# BlueBus.net
KiCad netlist of a schematic drawn in EAGLE
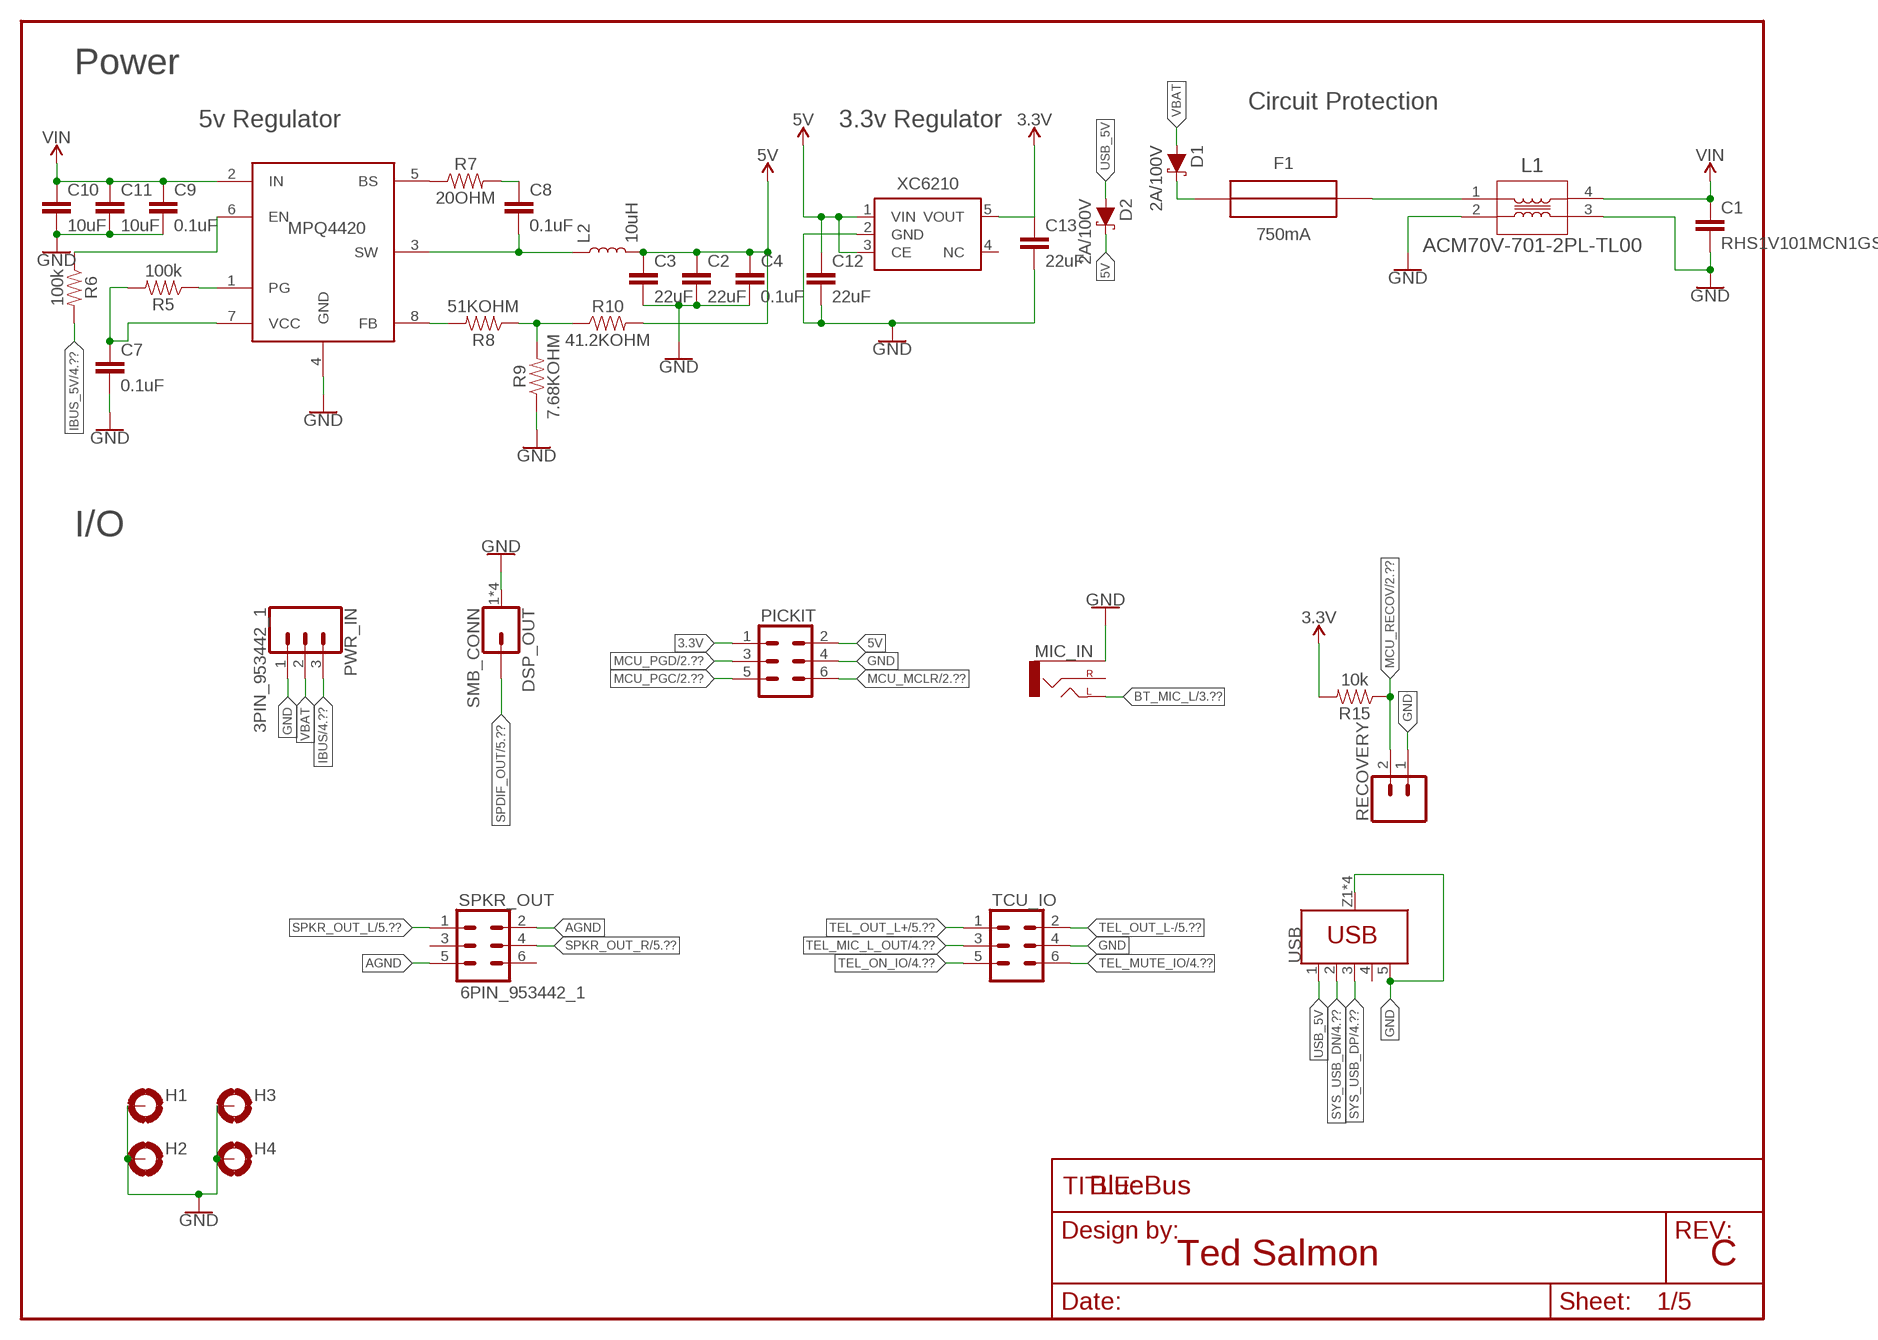
[diagram p0: schematic, sheet 1]
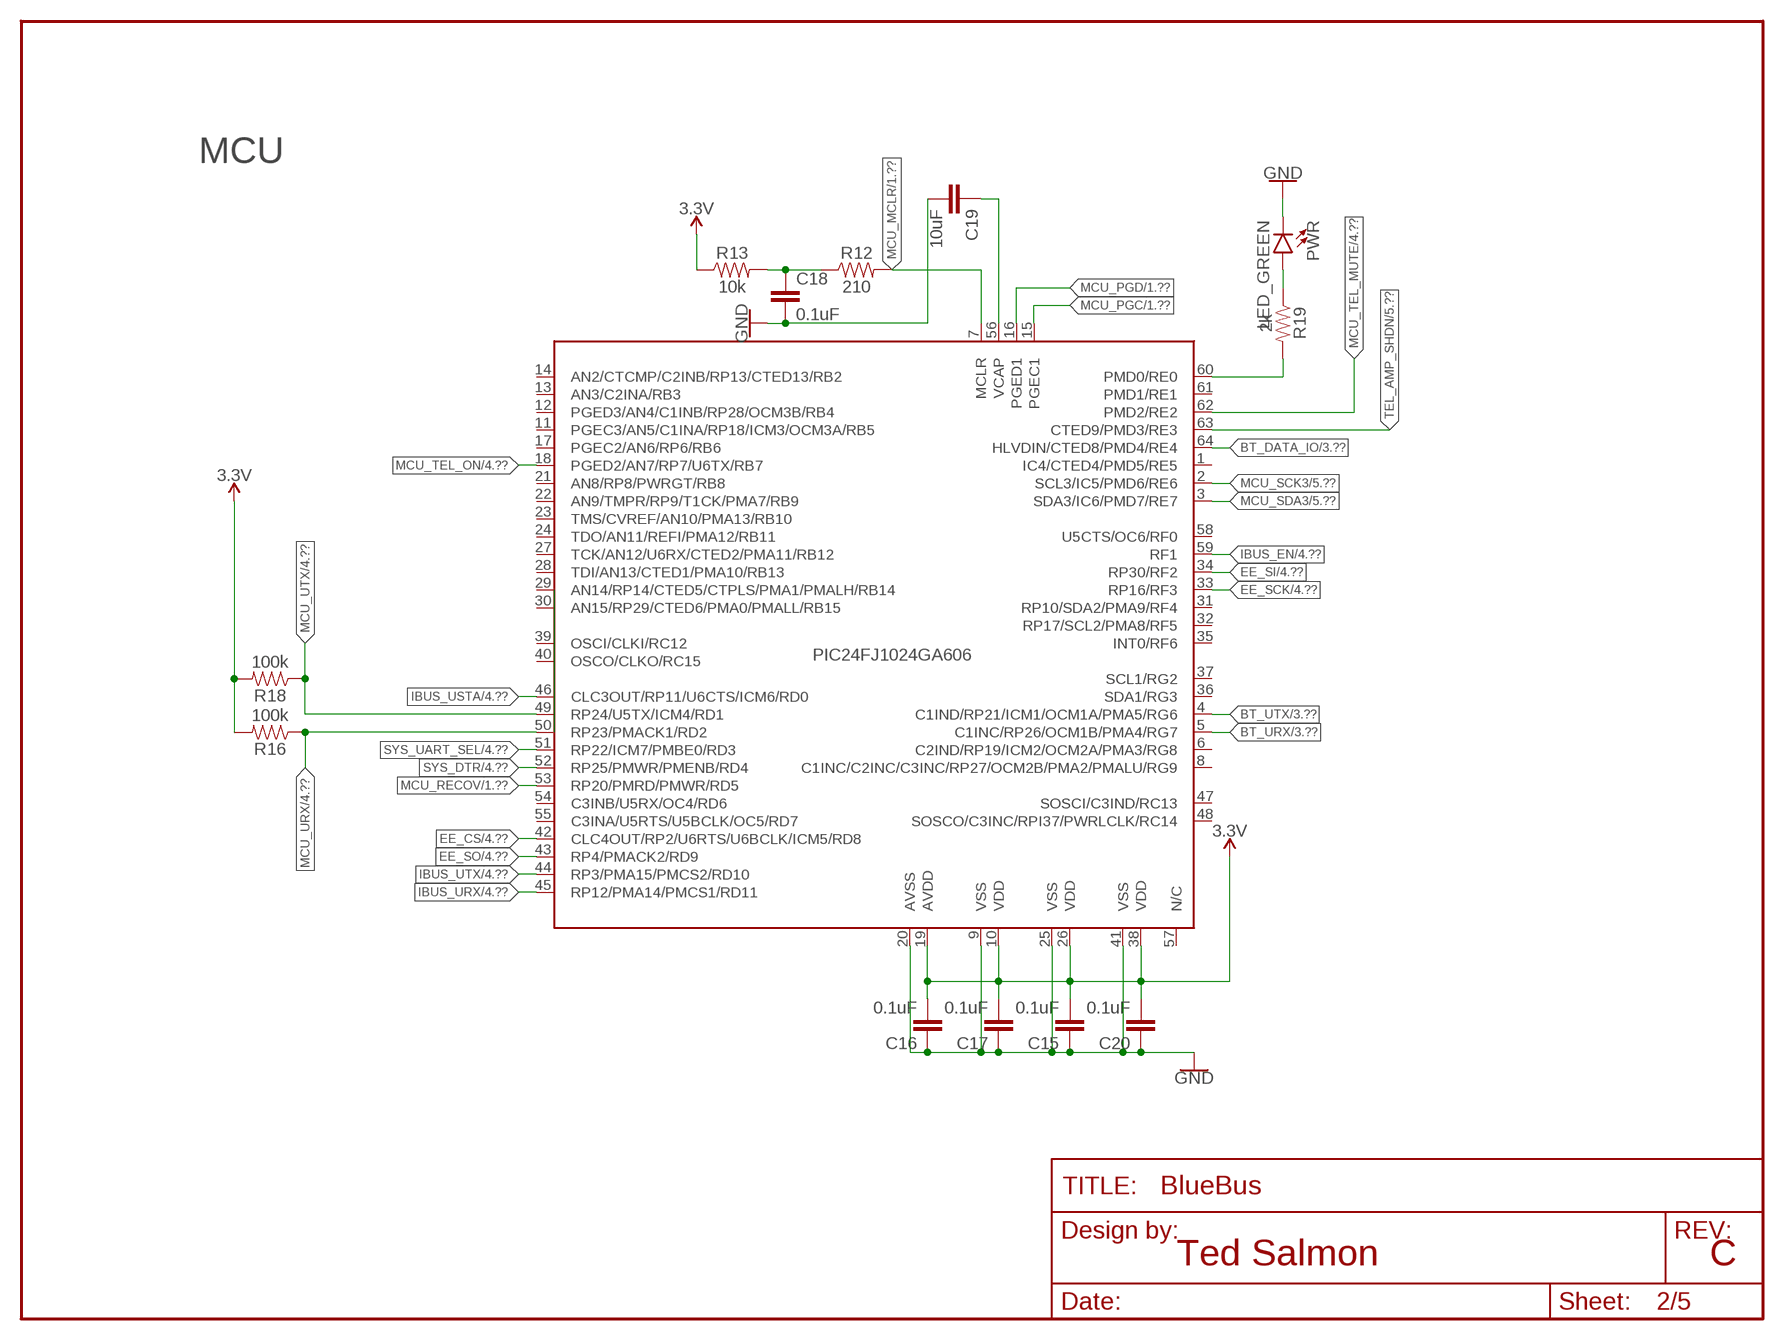
[diagram p1: schematic, sheet 2]
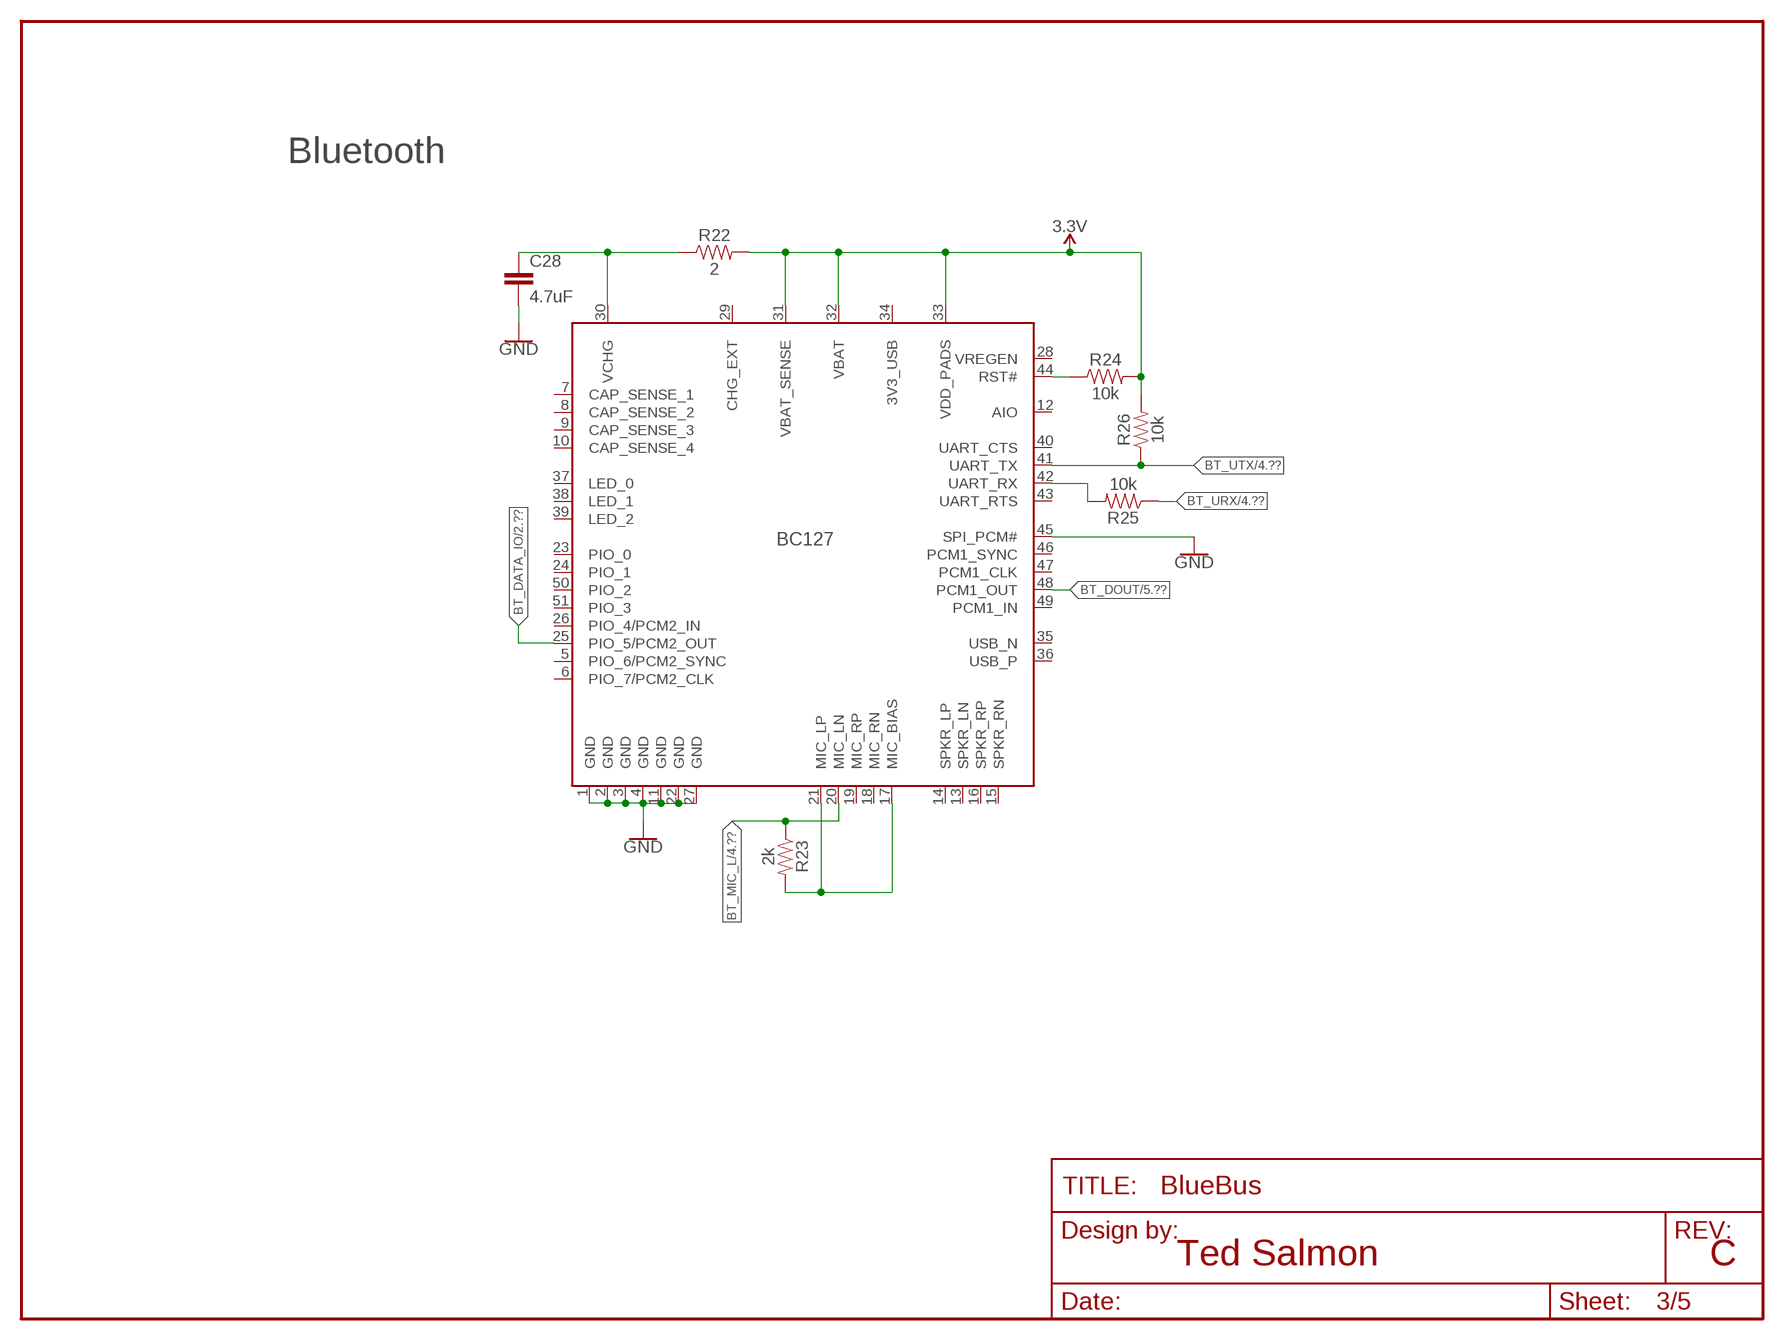
[diagram p2: schematic, sheet 3]
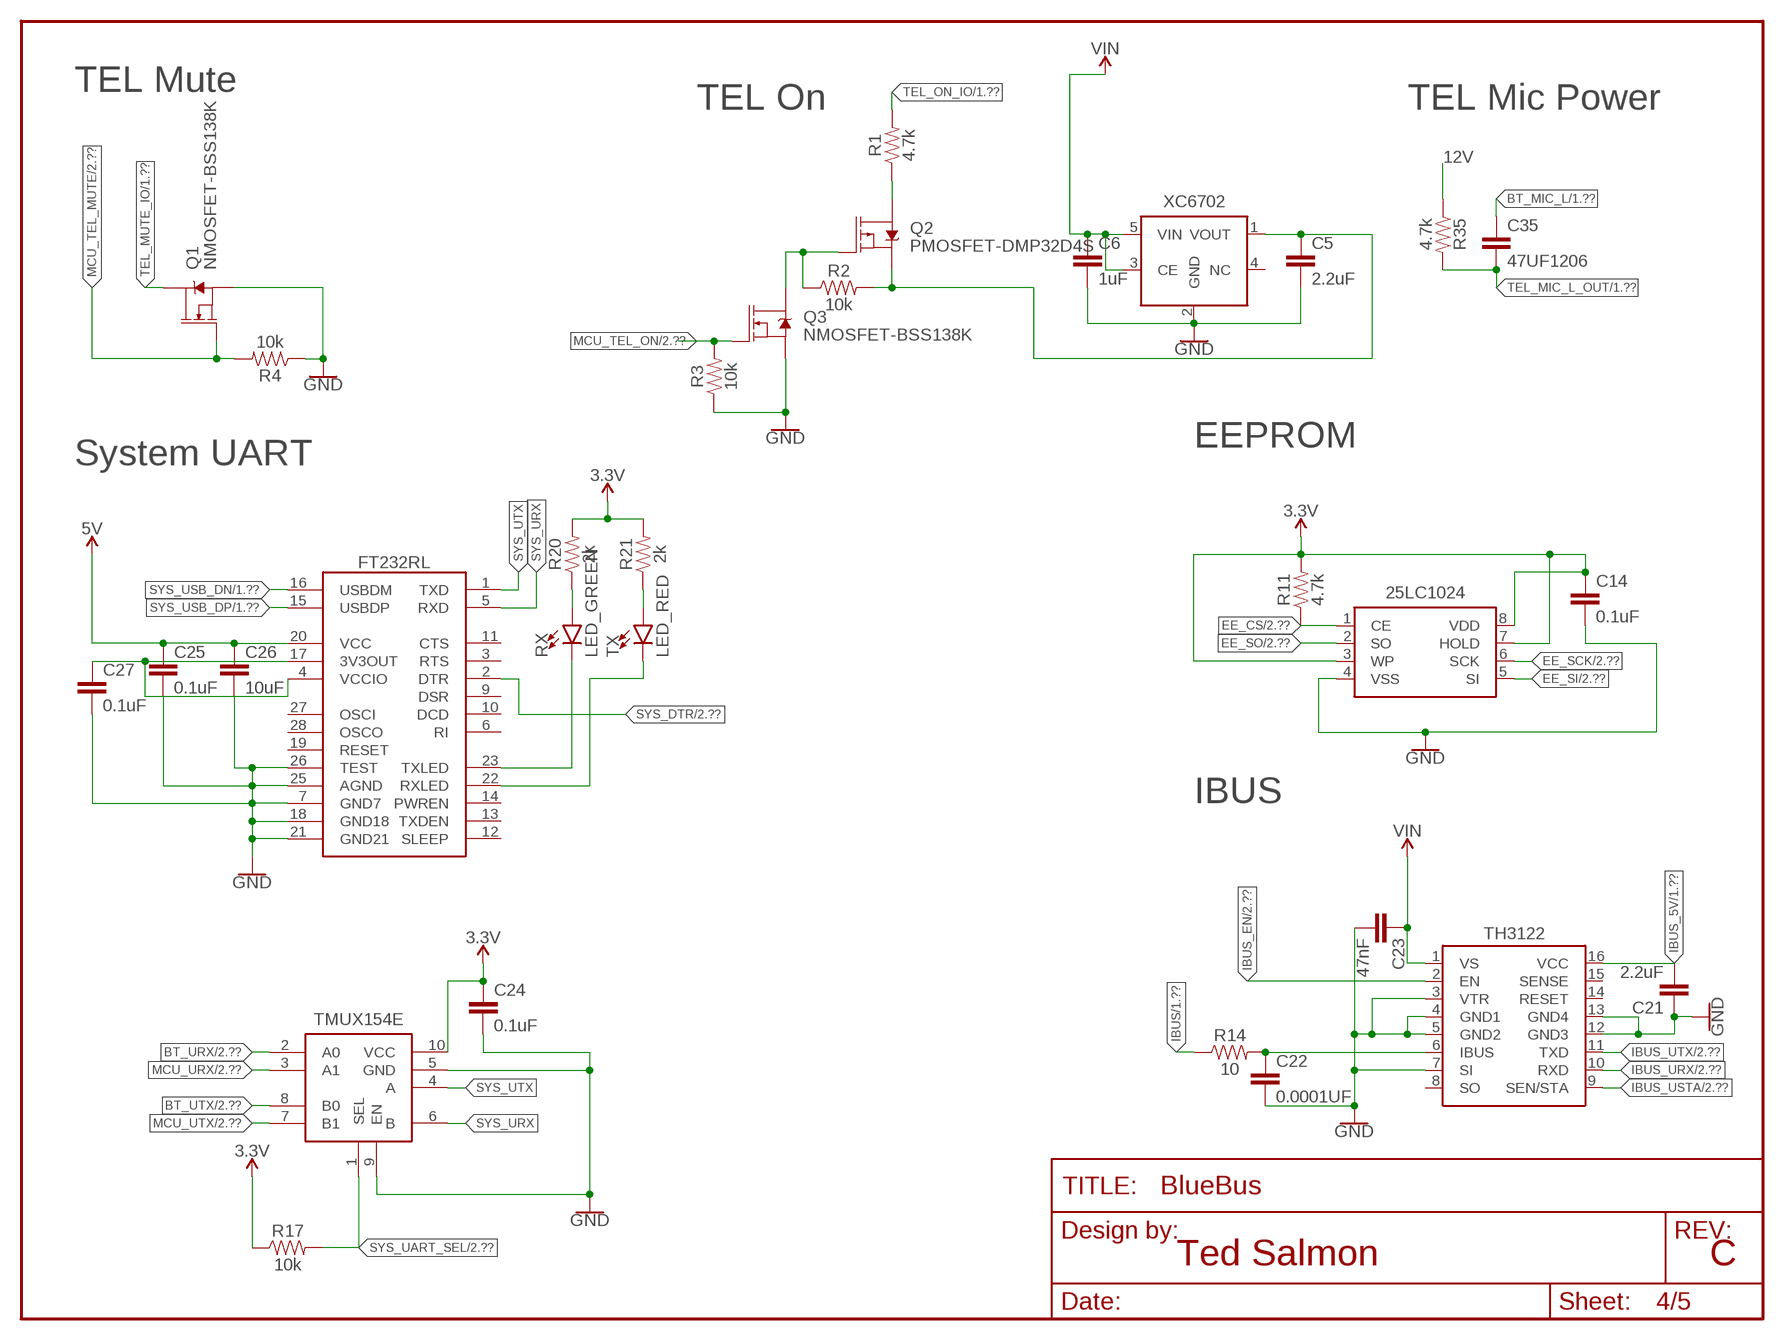
[diagram p3: schematic, sheet 4]
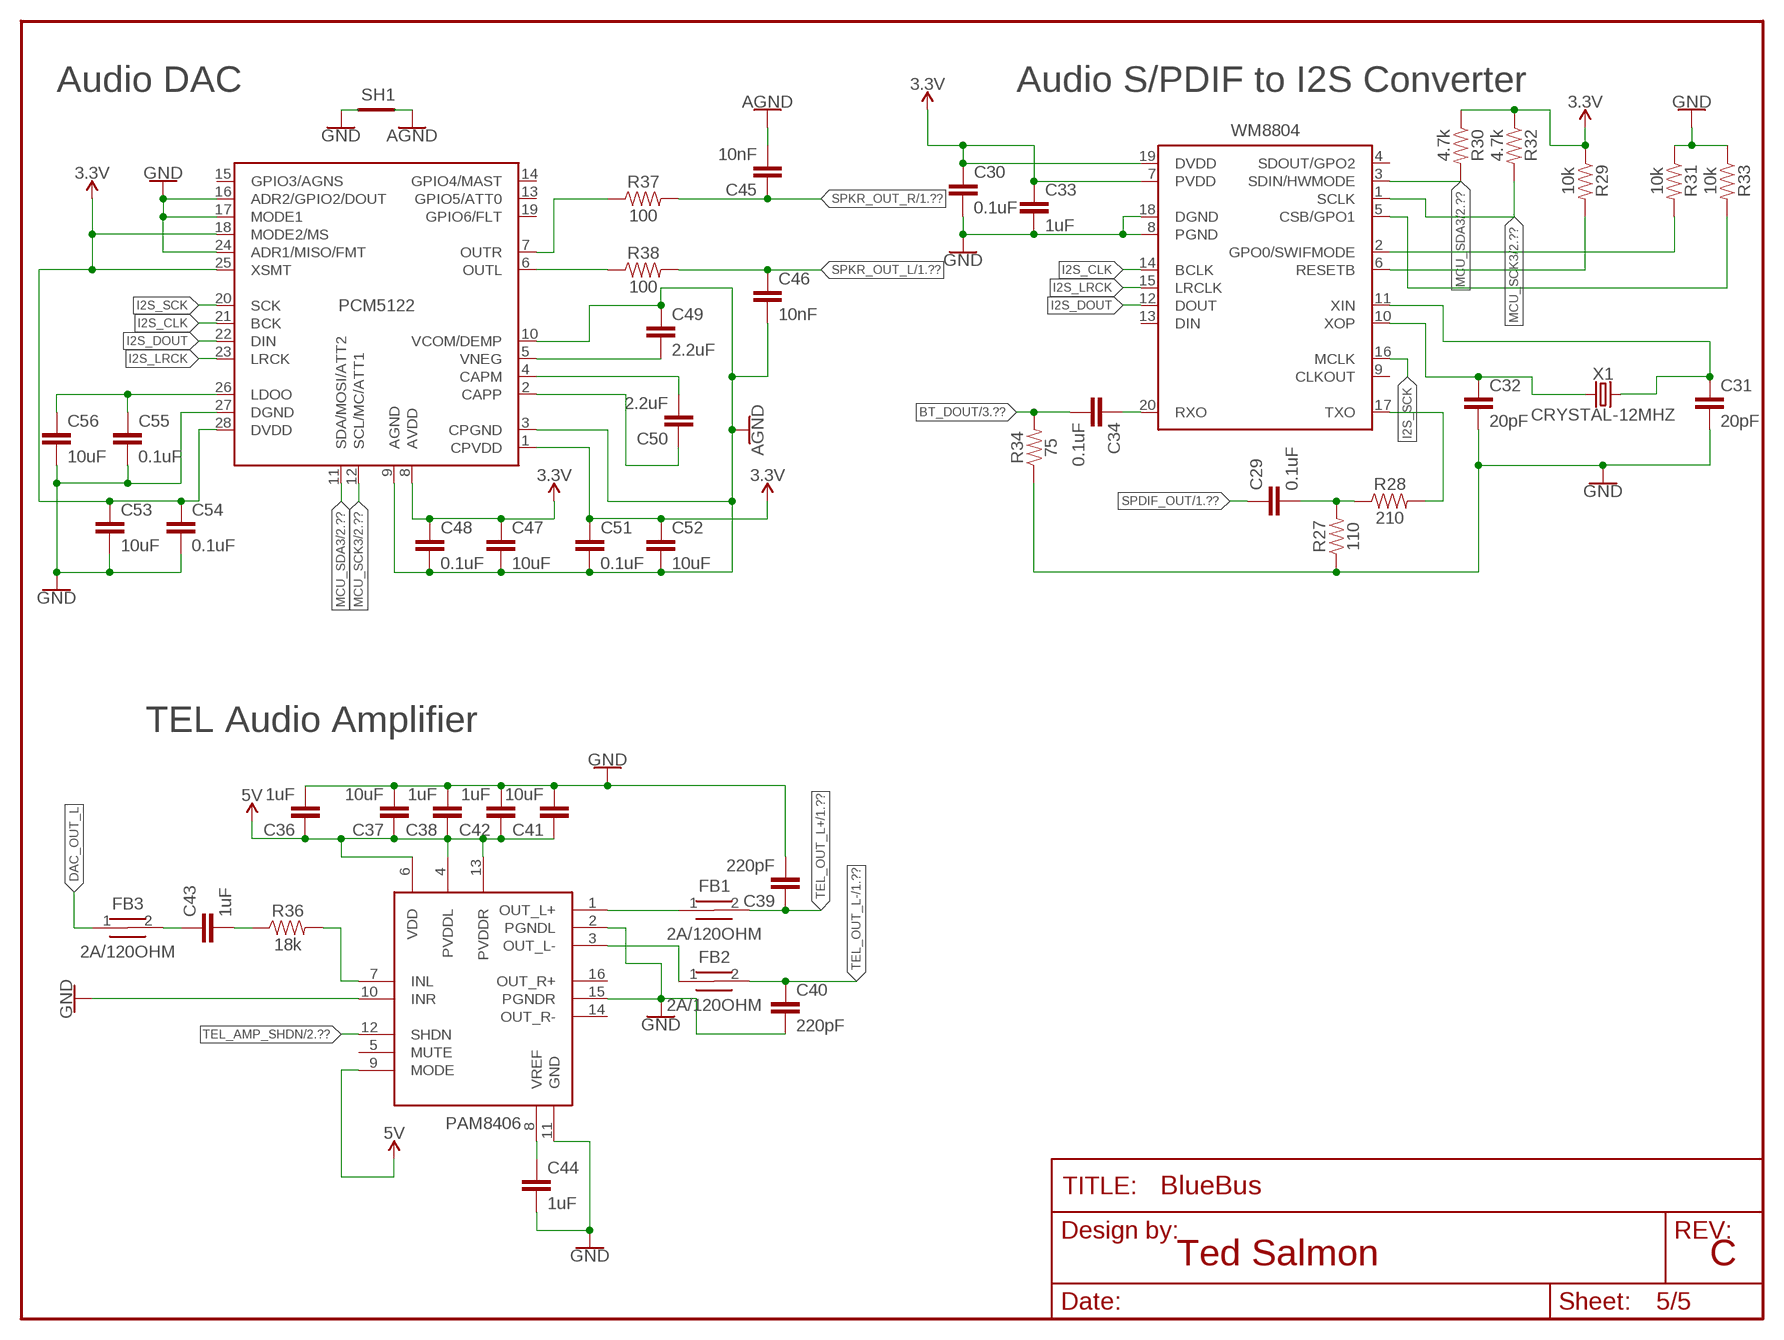
[diagram p4: schematic, sheet 5]

(export (version "E")
  (design (tool "Eeschema 10.0.6"))
  (components
    (comp (ref "BC127")
      (value "BC127")
      (footprint "eagle-import:BC127")
      (libsource (lib "eagle-import") (part "BC127"))
    )
    (comp (ref "C28")
      (value "4.7uF")
      (footprint "eagle-import:0805")
      (fields (field (name "MFG") "TDK"))
      (libsource (lib "eagle-import") (part "4.7UF"))
    )
    (comp (ref "FRAME4")
      (value "FRAME-LETTER")
      (footprint "eagle-import:DUMMY")
      (libsource (lib "eagle-import") (part "FRAME-LETTER"))
    )
    (comp (ref "R22")
      (value "2")
      (footprint "eagle-import:0805")
      (fields (field (name "MFG") "Panasonic"))
      (libsource (lib "eagle-import") (part "2OHM"))
    )
    (comp (ref "R23")
      (value "2k")
      (footprint "eagle-import:0805")
      (fields (field (name "MFG") "ROHM"))
      (libsource (lib "eagle-import") (part "2KOHM"))
    )
    (comp (ref "R24")
      (value "10k")
      (footprint "eagle-import:0805")
      (fields (field (name "MFG") "Panasonic"))
      (libsource (lib "eagle-import") (part "10KOHM"))
    )
    (comp (ref "R25")
      (value "10k")
      (footprint "eagle-import:0805")
      (fields (field (name "MFG") "Panasonic"))
      (libsource (lib "eagle-import") (part "10KOHM"))
    )
    (comp (ref "R26")
      (value "10k")
      (footprint "eagle-import:0805")
      (fields (field (name "MFG") "Panasonic"))
      (libsource (lib "eagle-import") (part "10KOHM"))
    )
    (comp (ref "25LC1024")
      (value "25LC1024")
      (footprint "eagle-import:SOIJ-8")
      (libsource (lib "eagle-import") (part "25LC1024"))
    )
    (comp (ref "C5")
      (value "2.2uF")
      (footprint "eagle-import:0805")
      (fields (field (name "MFG") "TDK"))
      (libsource (lib "eagle-import") (part "2.2UF"))
    )
    (comp (ref "C6")
      (value "1uF")
      (footprint "eagle-import:0805")
      (fields (field (name "MFG") "TDK"))
      (libsource (lib "eagle-import") (part "1UF"))
    )
    (comp (ref "C14")
      (value "0.1uF")
      (footprint "eagle-import:0805")
      (fields (field (name "MFG") "KEMET"))
      (libsource (lib "eagle-import") (part "0.1UF"))
    )
    (comp (ref "C21")
      (value "2.2uF")
      (footprint "eagle-import:0805")
      (fields (field (name "MFG") "TDK"))
      (libsource (lib "eagle-import") (part "2.2UF"))
    )
    (comp (ref "C22")
      (value "0.0001UF")
      (footprint "eagle-import:0805")
      (libsource (lib "eagle-import") (part "0.0001UF"))
    )
    (comp (ref "C23")
      (value "47nF")
      (footprint "eagle-import:0805")
      (fields (field (name "MFG") "AVX"))
      (libsource (lib "eagle-import") (part "47NF"))
    )
    (comp (ref "C24")
      (value "0.1uF")
      (footprint "eagle-import:0805")
      (fields (field (name "MFG") "KEMET"))
      (libsource (lib "eagle-import") (part "0.1UF"))
    )
    (comp (ref "C25")
      (value "0.1uF")
      (footprint "eagle-import:0805")
      (fields (field (name "MFG") "KEMET"))
      (libsource (lib "eagle-import") (part "0.1UF"))
    )
    (comp (ref "C26")
      (value "10uF")
      (footprint "eagle-import:0805")
      (fields (field (name "MFG") "TDK"))
      (libsource (lib "eagle-import") (part "10UF2012"))
    )
    (comp (ref "C27")
      (value "0.1uF")
      (footprint "eagle-import:0805")
      (fields (field (name "MFG") "KEMET"))
      (libsource (lib "eagle-import") (part "0.1UF"))
    )
    (comp (ref "C35")
      (value "47UF1206")
      (footprint "eagle-import:1206")
      (fields (field (name "MFG") "MURATA"))
      (libsource (lib "eagle-import") (part "47UF1206"))
    )
    (comp (ref "FRAME3")
      (value "FRAME-LETTER")
      (footprint "eagle-import:DUMMY")
      (libsource (lib "eagle-import") (part "FRAME-LETTER"))
    )
    (comp (ref "FT232RL")
      (value "FT232RL")
      (footprint "eagle-import:SSOP28")
      (libsource (lib "eagle-import") (part "FT232RL"))
    )
    (comp (ref "Q1")
      (value "NMOSFET-BSS138K")
      (footprint "eagle-import:SOT-23")
      (libsource (lib "eagle-import") (part "NMOSFET-BSS138K"))
    )
    (comp (ref "Q2")
      (value "PMOSFET-DMP32D4S")
      (footprint "eagle-import:SOT-23")
      (fields (field (name "MFG") "Diodes Inc") (field (name "MPN") "DMP32D4S"))
      (libsource (lib "eagle-import") (part "PMOSFET-DMP32D4S"))
    )
    (comp (ref "Q3")
      (value "NMOSFET-BSS138K")
      (footprint "eagle-import:SOT-23")
      (libsource (lib "eagle-import") (part "NMOSFET-BSS138K"))
    )
    (comp (ref "R1")
      (value "4.7k")
      (footprint "eagle-import:0805")
      (fields (field (name "MFG") "Panasonic"))
      (libsource (lib "eagle-import") (part "4.7KOHM"))
    )
    (comp (ref "R2")
      (value "10k")
      (footprint "eagle-import:0805")
      (fields (field (name "MFG") "Panasonic"))
      (libsource (lib "eagle-import") (part "10KOHM"))
    )
    (comp (ref "R3")
      (value "10k")
      (footprint "eagle-import:0805")
      (fields (field (name "MFG") "Panasonic"))
      (libsource (lib "eagle-import") (part "10KOHM"))
    )
    (comp (ref "R4")
      (value "10k")
      (footprint "eagle-import:0805")
      (fields (field (name "MFG") "Panasonic"))
      (libsource (lib "eagle-import") (part "10KOHM"))
    )
    (comp (ref "R11")
      (value "4.7k")
      (footprint "eagle-import:0805")
      (fields (field (name "MFG") "Panasonic"))
      (libsource (lib "eagle-import") (part "4.7KOHM"))
    )
    (comp (ref "R14")
      (value "10")
      (footprint "eagle-import:0805")
      (fields (field (name "MFG") "Panasonic"))
      (libsource (lib "eagle-import") (part "10OHM"))
    )
    (comp (ref "R17")
      (value "10k")
      (footprint "eagle-import:0805")
      (fields (field (name "MFG") "Panasonic"))
      (libsource (lib "eagle-import") (part "10KOHM"))
    )
    (comp (ref "R20")
      (value "2k")
      (footprint "eagle-import:0805")
      (fields (field (name "MFG") "ROHM"))
      (libsource (lib "eagle-import") (part "2KOHM"))
    )
    (comp (ref "R21")
      (value "2k")
      (footprint "eagle-import:0805")
      (fields (field (name "MFG") "ROHM"))
      (libsource (lib "eagle-import") (part "2KOHM"))
    )
    (comp (ref "R35")
      (value "4.7k")
      (footprint "eagle-import:0805")
      (fields (field (name "MFG") "Panasonic"))
      (libsource (lib "eagle-import") (part "4.7KOHM"))
    )
    (comp (ref "RX")
      (value "LED_GREEN")
      (footprint "eagle-import:LED-0805")
      (libsource (lib "eagle-import") (part "LED_GREEN"))
    )
    (comp (ref "TH3122")
      (value "TH3122.4")
      (footprint "eagle-import:SOIC16DF")
      (libsource (lib "eagle-import") (part "TH3122.4"))
    )
    (comp (ref "TMUX154E")
      (value "TMUX154E")
      (footprint "eagle-import:VSSOP10")
      (libsource (lib "eagle-import") (part "TMUX154E"))
    )
    (comp (ref "TX")
      (value "LED_RED")
      (footprint "eagle-import:LED-0805")
      (libsource (lib "eagle-import") (part "LED_RED"))
    )
    (comp (ref "XC6702")
      (value "XC6702DC018PR-G")
      (footprint "eagle-import:SOT-89-5")
      (libsource (lib "eagle-import") (part "XC6702DC018PR-G"))
    )
    (comp (ref "C15")
      (value "0.1uF")
      (footprint "eagle-import:0805")
      (fields (field (name "MFG") "KEMET"))
      (libsource (lib "eagle-import") (part "0.1UF"))
    )
    (comp (ref "C16")
      (value "0.1uF")
      (footprint "eagle-import:0805")
      (fields (field (name "MFG") "KEMET"))
      (libsource (lib "eagle-import") (part "0.1UF"))
    )
    (comp (ref "C17")
      (value "0.1uF")
      (footprint "eagle-import:0805")
      (fields (field (name "MFG") "KEMET"))
      (libsource (lib "eagle-import") (part "0.1UF"))
    )
    (comp (ref "C18")
      (value "0.1uF")
      (footprint "eagle-import:0805")
      (fields (field (name "MFG") "KEMET"))
      (libsource (lib "eagle-import") (part "0.1UF"))
    )
    (comp (ref "C19")
      (value "10uF")
      (footprint "eagle-import:0805")
      (fields (field (name "MFG") "TDK"))
      (libsource (lib "eagle-import") (part "10UF2012"))
    )
    (comp (ref "C20")
      (value "0.1uF")
      (footprint "eagle-import:0805")
      (fields (field (name "MFG") "KEMET"))
      (libsource (lib "eagle-import") (part "0.1UF"))
    )
    (comp (ref "FRAME2")
      (value "FRAME-LETTER")
      (footprint "eagle-import:DUMMY")
      (libsource (lib "eagle-import") (part "FRAME-LETTER"))
    )
    (comp (ref "PIC24FJ1024GA606")
      (value "PIC24FJ1024GA606")
      (footprint "eagle-import:TQFP64")
      (libsource (lib "eagle-import") (part "PIC24FJ1024GA606"))
    )
    (comp (ref "PWR")
      (value "LED_GREEN")
      (footprint "eagle-import:LED-0805")
      (libsource (lib "eagle-import") (part "LED_GREEN"))
    )
    (comp (ref "R12")
      (value "210")
      (footprint "eagle-import:0805")
      (libsource (lib "eagle-import") (part "210OHM"))
    )
    (comp (ref "R13")
      (value "10k")
      (footprint "eagle-import:0805")
      (fields (field (name "MFG") "Panasonic"))
      (libsource (lib "eagle-import") (part "10KOHM"))
    )
    (comp (ref "R16")
      (value "100k")
      (footprint "eagle-import:0805")
      (libsource (lib "eagle-import") (part "100KOHM"))
    )
    (comp (ref "R18")
      (value "100k")
      (footprint "eagle-import:0805")
      (libsource (lib "eagle-import") (part "100KOHM"))
    )
    (comp (ref "R19")
      (value "2k")
      (footprint "eagle-import:0805")
      (fields (field (name "MFG") "ROHM"))
      (libsource (lib "eagle-import") (part "2KOHM"))
    )
    (comp (ref "C1")
      (value "RHS1V101MCN1GS")
      (footprint "eagle-import:RHS1V101MCN1GS")
      (fields (field (name "MFG") "Nichicon"))
      (libsource (lib "eagle-import") (part "RHS1V101MCN1GS"))
    )
    (comp (ref "C2")
      (value "22uF")
      (footprint "eagle-import:0805")
      (fields (field (name "MFG") "TDK"))
      (libsource (lib "eagle-import") (part "22UF"))
    )
    (comp (ref "C3")
      (value "22uF")
      (footprint "eagle-import:0805")
      (fields (field (name "MFG") "TDK"))
      (libsource (lib "eagle-import") (part "22UF"))
    )
    (comp (ref "C4")
      (value "0.1uF")
      (footprint "eagle-import:0805")
      (fields (field (name "MFG") "KEMET"))
      (libsource (lib "eagle-import") (part "0.1UF"))
    )
    (comp (ref "C7")
      (value "0.1uF")
      (footprint "eagle-import:0805")
      (fields (field (name "MFG") "KEMET"))
      (libsource (lib "eagle-import") (part "0.1UF"))
    )
    (comp (ref "C8")
      (value "0.1uF")
      (footprint "eagle-import:0805")
      (fields (field (name "MFG") "KEMET"))
      (libsource (lib "eagle-import") (part "0.1UF"))
    )
    (comp (ref "C9")
      (value "0.1uF")
      (footprint "eagle-import:0805")
      (fields (field (name "MFG") "KEMET"))
      (libsource (lib "eagle-import") (part "0.1UF"))
    )
    (comp (ref "C10")
      (value "10uF")
      (footprint "eagle-import:1206")
      (fields (field (name "MFG") "TDK"))
      (libsource (lib "eagle-import") (part "10UF"))
    )
    (comp (ref "C11")
      (value "10uF")
      (footprint "eagle-import:1206")
      (fields (field (name "MFG") "TDK"))
      (libsource (lib "eagle-import") (part "10UF"))
    )
    (comp (ref "C12")
      (value "22uF")
      (footprint "eagle-import:0805")
      (fields (field (name "MFG") "TDK"))
      (libsource (lib "eagle-import") (part "22UF"))
    )
    (comp (ref "C13")
      (value "22uF")
      (footprint "eagle-import:0805")
      (fields (field (name "MFG") "TDK"))
      (libsource (lib "eagle-import") (part "22UF"))
    )
    (comp (ref "D1")
      (value "2A/100V")
      (footprint "eagle-import:SOD123")
      (fields (field (name "MFG") "STMicroelectronics"))
      (libsource (lib "eagle-import") (part "SCHOTTKYDIODE2A100V"))
    )
    (comp (ref "D2")
      (value "2A/100V")
      (footprint "eagle-import:SOD123")
      (fields (field (name "MFG") "STMicroelectronics"))
      (libsource (lib "eagle-import") (part "SCHOTTKYDIODE2A100V"))
    )
    (comp (ref "DSP_OUT")
      (value "SMB_CONN")
      (footprint "eagle-import:MOLEX_SMB")
      (libsource (lib "eagle-import") (part "SMB_CONN"))
    )
    (comp (ref "F1")
      (value "750mA")
      (footprint "eagle-import:LITTLEFUSE")
      (fields (field (name "MFG") "LITTLEBLOCK"))
      (libsource (lib "eagle-import") (part "LITTLEBLOCK_FUSE_.75A"))
    )
    (comp (ref "FRAME1")
      (value "FRAME-LETTER")
      (footprint "eagle-import:DUMMY")
      (libsource (lib "eagle-import") (part "FRAME-LETTER"))
    )
    (comp (ref "H1")
      (value "2,0-PAD")
      (footprint "eagle-import:2.0-PAD")
      (libsource (lib "eagle-import") (part "2,0-PAD"))
    )
    (comp (ref "H2")
      (value "2,0-PAD")
      (footprint "eagle-import:2.0-PAD")
      (libsource (lib "eagle-import") (part "2,0-PAD"))
    )
    (comp (ref "H3")
      (value "2,0-PAD")
      (footprint "eagle-import:2.0-PAD")
      (libsource (lib "eagle-import") (part "2,0-PAD"))
    )
    (comp (ref "H4")
      (value "2,0-PAD")
      (footprint "eagle-import:2.0-PAD")
      (libsource (lib "eagle-import") (part "2,0-PAD"))
    )
    (comp (ref "L1")
      (value "ACM70V-701-2PL-TL00")
      (footprint "eagle-import:ACM70V-701-2PL-TL00")
      (fields (field (name "MFG") "TDK"))
      (libsource (lib "eagle-import") (part "ACM70V-701-2PL-TL00"))
    )
    (comp (ref "L2")
      (value "10uH")
      (footprint "eagle-import:MPL-SE5040")
      (fields (field (name "MFG") "MPS"))
      (libsource (lib "eagle-import") (part "MPL-SE5040-100"))
    )
    (comp (ref "MIC_IN")
      (value "AUDIO-CUI-SJ-3523-SMT")
      (footprint "eagle-import:AUDIO-CUI-SJ-352X-SMT")
      (libsource (lib "eagle-import") (part "AUDIO-CUI-SJ-3523-SMT"))
    )
    (comp (ref "MPQ4420")
      (value "MPQ4420")
      (footprint "eagle-import:TSOT23-8")
      (libsource (lib "eagle-import") (part "MPQ4420"))
    )
    (comp (ref "PICKIT")
      (value "6PIN_JUMPER")
      (footprint "eagle-import:2X3")
      (libsource (lib "eagle-import") (part "6PIN_JUMPER"))
    )
    (comp (ref "PWR_IN")
      (value "3PIN_953442_1")
      (footprint "eagle-import:TE_MQS_3PIN")
      (libsource (lib "eagle-import") (part "3PIN_953442_1"))
    )
    (comp (ref "R5")
      (value "100k")
      (footprint "eagle-import:0805")
      (libsource (lib "eagle-import") (part "100KOHM"))
    )
    (comp (ref "R6")
      (value "100k")
      (footprint "eagle-import:0805")
      (libsource (lib "eagle-import") (part "100KOHM"))
    )
    (comp (ref "R7")
      (value "20OHM")
      (footprint "eagle-import:0805")
      (libsource (lib "eagle-import") (part "20OHM"))
    )
    (comp (ref "R8")
      (value "51KOHM")
      (footprint "eagle-import:0805")
      (libsource (lib "eagle-import") (part "51KOHM"))
    )
    (comp (ref "R9")
      (value "7.68KOHM")
      (footprint "eagle-import:0805")
      (libsource (lib "eagle-import") (part "7.68KOHM"))
    )
    (comp (ref "R10")
      (value "41.2KOHM")
      (footprint "eagle-import:0805")
      (libsource (lib "eagle-import") (part "41.2KOHM"))
    )
    (comp (ref "R15")
      (value "10k")
      (footprint "eagle-import:0805")
      (fields (field (name "MFG") "Panasonic"))
      (libsource (lib "eagle-import") (part "10KOHM"))
    )
    (comp (ref "RECOVERY")
      (value "2PIN_JUMPER")
      (footprint "eagle-import:1X02")
      (libsource (lib "eagle-import") (part "2PIN_JUMPER"))
    )
    (comp (ref "SPKR_OUT")
      (value "6PIN_953442_1")
      (footprint "eagle-import:TE_MQS_6PIN")
      (libsource (lib "eagle-import") (part "6PIN_953442_1"))
    )
    (comp (ref "TCU_IO")
      (value "6PIN_5_103166_1")
      (footprint "eagle-import:TE_AMPMODU_6_PIN")
      (libsource (lib "eagle-import") (part "6PIN_5_103166_1"))
    )
    (comp (ref "USB")
      (value "USB_WURTH_629105150521")
      (footprint "eagle-import:629105150521")
      (libsource (lib "eagle-import") (part "USB_WURTH_629105150521"))
    )
    (comp (ref "XC6210")
      (value "XC6210SOT25")
      (footprint "eagle-import:SOT23-5")
      (libsource (lib "eagle-import") (part "XC6210SOT25"))
    )
    (comp (ref "C29")
      (value "0.1uF")
      (footprint "eagle-import:0805")
      (fields (field (name "MFG") "KEMET"))
      (libsource (lib "eagle-import") (part "0.1UF"))
    )
    (comp (ref "C30")
      (value "0.1uF")
      (footprint "eagle-import:0805")
      (fields (field (name "MFG") "KEMET"))
      (libsource (lib "eagle-import") (part "0.1UF"))
    )
    (comp (ref "C31")
      (value "20pF")
      (footprint "eagle-import:0805")
      (libsource (lib "eagle-import") (part "20PF"))
    )
    (comp (ref "C32")
      (value "20pF")
      (footprint "eagle-import:0805")
      (libsource (lib "eagle-import") (part "20PF"))
    )
    (comp (ref "C33")
      (value "1uF")
      (footprint "eagle-import:0805")
      (fields (field (name "MFG") "TDK"))
      (libsource (lib "eagle-import") (part "1UF"))
    )
    (comp (ref "C34")
      (value "0.1uF")
      (footprint "eagle-import:0805")
      (fields (field (name "MFG") "KEMET"))
      (libsource (lib "eagle-import") (part "0.1UF"))
    )
    (comp (ref "C36")
      (value "1uF")
      (footprint "eagle-import:0805")
      (fields (field (name "MFG") "TDK"))
      (libsource (lib "eagle-import") (part "1UF"))
    )
    (comp (ref "C37")
      (value "10uF")
      (footprint "eagle-import:0805")
      (fields (field (name "MFG") "TDK"))
      (libsource (lib "eagle-import") (part "10UF2012"))
    )
    (comp (ref "C38")
      (value "1uF")
      (footprint "eagle-import:0805")
      (fields (field (name "MFG") "TDK"))
      (libsource (lib "eagle-import") (part "1UF"))
    )
    (comp (ref "C39")
      (value "220pF")
      (footprint "eagle-import:0805")
      (fields (field (name "MFG") "KEMET"))
      (libsource (lib "eagle-import") (part "220PF"))
    )
    (comp (ref "C40")
      (value "220pF")
      (footprint "eagle-import:0805")
      (fields (field (name "MFG") "KEMET"))
      (libsource (lib "eagle-import") (part "220PF"))
    )
    (comp (ref "C41")
      (value "10uF")
      (footprint "eagle-import:0805")
      (fields (field (name "MFG") "TDK"))
      (libsource (lib "eagle-import") (part "10UF2012"))
    )
    (comp (ref "C42")
      (value "1uF")
      (footprint "eagle-import:0805")
      (fields (field (name "MFG") "TDK"))
      (libsource (lib "eagle-import") (part "1UF"))
    )
    (comp (ref "C43")
      (value "1uF")
      (footprint "eagle-import:0805")
      (fields (field (name "MFG") "TDK"))
      (libsource (lib "eagle-import") (part "1UF"))
    )
    (comp (ref "C44")
      (value "1uF")
      (footprint "eagle-import:0805")
      (fields (field (name "MFG") "TDK"))
      (libsource (lib "eagle-import") (part "1UF"))
    )
    (comp (ref "C45")
      (value "10nF")
      (footprint "eagle-import:0805")
      (fields (field (name "MFG") "KEMET"))
      (libsource (lib "eagle-import") (part "10NF"))
    )
    (comp (ref "C46")
      (value "10nF")
      (footprint "eagle-import:0805")
      (fields (field (name "MFG") "KEMET"))
      (libsource (lib "eagle-import") (part "10NF"))
    )
    (comp (ref "C47")
      (value "10uF")
      (footprint "eagle-import:0805")
      (fields (field (name "MFG") "TDK"))
      (libsource (lib "eagle-import") (part "10UF2012"))
    )
    (comp (ref "C48")
      (value "0.1uF")
      (footprint "eagle-import:0805")
      (fields (field (name "MFG") "KEMET"))
      (libsource (lib "eagle-import") (part "0.1UF"))
    )
    (comp (ref "C49")
      (value "2.2uF")
      (footprint "eagle-import:0805")
      (fields (field (name "MFG") "TDK"))
      (libsource (lib "eagle-import") (part "2.2UF"))
    )
    (comp (ref "C50")
      (value "2.2uF")
      (footprint "eagle-import:0805")
      (fields (field (name "MFG") "TDK"))
      (libsource (lib "eagle-import") (part "2.2UF"))
    )
    (comp (ref "C51")
      (value "0.1uF")
      (footprint "eagle-import:0805")
      (fields (field (name "MFG") "KEMET"))
      (libsource (lib "eagle-import") (part "0.1UF"))
    )
    (comp (ref "C52")
      (value "10uF")
      (footprint "eagle-import:0805")
      (fields (field (name "MFG") "TDK"))
      (libsource (lib "eagle-import") (part "10UF2012"))
    )
    (comp (ref "C53")
      (value "10uF")
      (footprint "eagle-import:0805")
      (fields (field (name "MFG") "TDK"))
      (libsource (lib "eagle-import") (part "10UF2012"))
    )
    (comp (ref "C54")
      (value "0.1uF")
      (footprint "eagle-import:0805")
      (fields (field (name "MFG") "KEMET"))
      (libsource (lib "eagle-import") (part "0.1UF"))
    )
    (comp (ref "C55")
      (value "0.1uF")
      (footprint "eagle-import:0805")
      (fields (field (name "MFG") "KEMET"))
      (libsource (lib "eagle-import") (part "0.1UF"))
    )
    (comp (ref "C56")
      (value "10uF")
      (footprint "eagle-import:0805")
      (fields (field (name "MFG") "TDK"))
      (libsource (lib "eagle-import") (part "10UF2012"))
    )
    (comp (ref "FB1")
      (value "2A/120OHM")
      (footprint "eagle-import:0805")
      (fields (field (name "MFG") "BOURNS"))
      (libsource (lib "eagle-import") (part "FERRITE_2A/120OHM"))
    )
    (comp (ref "FB2")
      (value "2A/120OHM")
      (footprint "eagle-import:0805")
      (fields (field (name "MFG") "BOURNS"))
      (libsource (lib "eagle-import") (part "FERRITE_2A/120OHM"))
    )
    (comp (ref "FB3")
      (value "2A/120OHM")
      (footprint "eagle-import:0805")
      (fields (field (name "MFG") "BOURNS"))
      (libsource (lib "eagle-import") (part "FERRITE_2A/120OHM"))
    )
    (comp (ref "FRAME5")
      (value "FRAME-LETTER")
      (footprint "eagle-import:DUMMY")
      (libsource (lib "eagle-import") (part "FRAME-LETTER"))
    )
    (comp (ref "PAM8406")
      (value "PAM8406")
      (footprint "eagle-import:SOP-16")
      (libsource (lib "eagle-import") (part "PAM8406"))
    )
    (comp (ref "PCM5122")
      (value "PCM5122")
      (footprint "eagle-import:TSSOP28")
      (libsource (lib "eagle-import") (part "PCM5122"))
    )
    (comp (ref "R27")
      (value "110")
      (footprint "eagle-import:0805")
      (libsource (lib "eagle-import") (part "110OHM"))
    )
    (comp (ref "R28")
      (value "210")
      (footprint "eagle-import:0805")
      (libsource (lib "eagle-import") (part "210OHM"))
    )
    (comp (ref "R29")
      (value "10k")
      (footprint "eagle-import:0805")
      (fields (field (name "MFG") "Panasonic"))
      (libsource (lib "eagle-import") (part "10KOHM"))
    )
    (comp (ref "R30")
      (value "4.7k")
      (footprint "eagle-import:0805")
      (fields (field (name "MFG") "Panasonic"))
      (libsource (lib "eagle-import") (part "4.7KOHM"))
    )
    (comp (ref "R31")
      (value "10k")
      (footprint "eagle-import:0805")
      (fields (field (name "MFG") "Panasonic"))
      (libsource (lib "eagle-import") (part "10KOHM"))
    )
    (comp (ref "R32")
      (value "4.7k")
      (footprint "eagle-import:0805")
      (fields (field (name "MFG") "Panasonic"))
      (libsource (lib "eagle-import") (part "4.7KOHM"))
    )
    (comp (ref "R33")
      (value "10k")
      (footprint "eagle-import:0805")
      (fields (field (name "MFG") "Panasonic"))
      (libsource (lib "eagle-import") (part "10KOHM"))
    )
    (comp (ref "R34")
      (value "75")
      (footprint "eagle-import:0805")
      (fields (field (name "MFG") "Panasonic"))
      (libsource (lib "eagle-import") (part "75OHM"))
    )
    (comp (ref "R36")
      (value "18k")
      (footprint "eagle-import:0805")
      (fields (field (name "MFG") "Panasonic"))
      (libsource (lib "eagle-import") (part "18KOHM"))
    )
    (comp (ref "R37")
      (value "100")
      (footprint "eagle-import:0805")
      (fields (field (name "MFG") "PANASONIC"))
      (libsource (lib "eagle-import") (part "100OHM"))
    )
    (comp (ref "R38")
      (value "100")
      (footprint "eagle-import:0805")
      (fields (field (name "MFG") "PANASONIC"))
      (libsource (lib "eagle-import") (part "100OHM"))
    )
    (comp (ref "SH1")
      (value "SHORTT5")
      (footprint "eagle-import:SHORT_TOP-50")
      (libsource (lib "eagle-import") (part "SHORTT5"))
    )
    (comp (ref "WM8804")
      (value "WM8804")
      (footprint "eagle-import:SSOP20")
      (libsource (lib "eagle-import") (part "WM8804"))
    )
    (comp (ref "X1")
      (value "CRYSTAL-12MHZ")
      (footprint "eagle-import:HC49")
      (libsource (lib "eagle-import") (part "CRYSTAL-12MHZ"))
    )
  )
  (nets
    (net (code "1") (name "3.3V") (class "Default")
      (node (ref "25LC1024") (pin "3") (pinfunction "WP_3") (pintype "bidirectional"))
      (node (ref "25LC1024") (pin "7") (pinfunction "HOLD_7") (pintype "bidirectional"))
      (node (ref "25LC1024") (pin "8") (pinfunction "VDD_8") (pintype "power_in"))
      (node (ref "BC127") (pin "31") (pinfunction "VBAT_SENSE_31") (pintype "power_in"))
      (node (ref "BC127") (pin "32") (pinfunction "VBAT_32") (pintype "bidirectional"))
      (node (ref "BC127") (pin "33") (pinfunction "VDD_PADS_33") (pintype "power_in"))
      (node (ref "C13") (pin "1") (pinfunction "1_1") (pintype "passive"))
      (node (ref "C14") (pin "1") (pinfunction "1_1") (pintype "passive"))
      (node (ref "C15") (pin "2") (pinfunction "2_2") (pintype "passive"))
      (node (ref "C16") (pin "2") (pinfunction "2_2") (pintype "passive"))
      (node (ref "C17") (pin "2") (pinfunction "2_2") (pintype "passive"))
      (node (ref "C20") (pin "2") (pinfunction "2_2") (pintype "passive"))
      (node (ref "C24") (pin "1") (pinfunction "1_1") (pintype "passive"))
      (node (ref "C30") (pin "1") (pinfunction "1_1") (pintype "passive"))
      (node (ref "C33") (pin "1") (pinfunction "1_1") (pintype "passive"))
      (node (ref "C47") (pin "1") (pinfunction "1_1") (pintype "passive"))
      (node (ref "C48") (pin "1") (pinfunction "1_1") (pintype "passive"))
      (node (ref "C51") (pin "1") (pinfunction "1_1") (pintype "passive"))
      (node (ref "C52") (pin "1") (pinfunction "1_1") (pintype "passive"))
      (node (ref "C53") (pin "1") (pinfunction "1_1") (pintype "passive"))
      (node (ref "C54") (pin "1") (pinfunction "1_1") (pintype "passive"))
      (node (ref "PCM5122") (pin "1") (pinfunction "CPVDD_1") (pintype "power_in"))
      (node (ref "PCM5122") (pin "18") (pinfunction "MODE2/MS_18") (pintype "bidirectional"))
      (node (ref "PCM5122") (pin "25") (pinfunction "XSMT_25") (pintype "input"))
      (node (ref "PCM5122") (pin "28") (pinfunction "DVDD_28") (pintype "power_in"))
      (node (ref "PCM5122") (pin "8") (pinfunction "AVDD_8") (pintype "power_in"))
      (node (ref "PIC24FJ1024GA606") (pin "10") (pinfunction "VDD_10") (pintype "power_in"))
      (node (ref "PIC24FJ1024GA606") (pin "19") (pinfunction "AVDD_19") (pintype "power_in"))
      (node (ref "PIC24FJ1024GA606") (pin "26") (pinfunction "VDD_26") (pintype "power_in"))
      (node (ref "PIC24FJ1024GA606") (pin "38") (pinfunction "VDD_38") (pintype "power_in"))
      (node (ref "PICKIT") (pin "1") (pinfunction "1_1") (pintype "bidirectional"))
      (node (ref "R11") (pin "2") (pinfunction "2_2") (pintype "passive"))
      (node (ref "R13") (pin "1") (pinfunction "1_1") (pintype "passive"))
      (node (ref "R15") (pin "2") (pinfunction "2_2") (pintype "passive"))
      (node (ref "R16") (pin "2") (pinfunction "2_2") (pintype "passive"))
      (node (ref "R17") (pin "1") (pinfunction "1_1") (pintype "passive"))
      (node (ref "R18") (pin "2") (pinfunction "2_2") (pintype "passive"))
      (node (ref "R20") (pin "2") (pinfunction "2_2") (pintype "passive"))
      (node (ref "R21") (pin "2") (pinfunction "2_2") (pintype "passive"))
      (node (ref "R22") (pin "2") (pinfunction "2_2") (pintype "passive"))
      (node (ref "R24") (pin "2") (pinfunction "2_2") (pintype "passive"))
      (node (ref "R26") (pin "2") (pinfunction "2_2") (pintype "passive"))
      (node (ref "R29") (pin "1") (pinfunction "1_1") (pintype "passive"))
      (node (ref "R30") (pin "1") (pinfunction "1_1") (pintype "passive"))
      (node (ref "R32") (pin "1") (pinfunction "1_1") (pintype "passive"))
      (node (ref "TMUX154E") (pin "10") (pinfunction "VCC_10") (pintype "power_in"))
      (node (ref "WM8804") (pin "19") (pinfunction "DVDD_19") (pintype "power_in"))
      (node (ref "WM8804") (pin "7") (pinfunction "PVDD_7") (pintype "power_in"))
      (node (ref "XC6210") (pin "5") (pinfunction "VOUT_5") (pintype "power_in"))
    )
    (net (code "2") (name "3V3_USB") (class "Default")
      (node (ref "BC127") (pin "34") (pinfunction "3V3_USB_34") (pintype "power_in"))
    )
    (net (code "3") (name "5V") (class "Default")
      (node (ref "C12") (pin "1") (pinfunction "1_1") (pintype "passive"))
      (node (ref "C2") (pin "1") (pinfunction "1_1") (pintype "passive"))
      (node (ref "C25") (pin "1") (pinfunction "1_1") (pintype "passive"))
      (node (ref "C26") (pin "1") (pinfunction "1_1") (pintype "passive"))
      (node (ref "C3") (pin "1") (pinfunction "1_1") (pintype "passive"))
      (node (ref "C36") (pin "1") (pinfunction "1_1") (pintype "passive"))
      (node (ref "C37") (pin "1") (pinfunction "1_1") (pintype "passive"))
      (node (ref "C38") (pin "1") (pinfunction "1_1") (pintype "passive"))
      (node (ref "C4") (pin "1") (pinfunction "1_1") (pintype "passive"))
      (node (ref "C41") (pin "1") (pinfunction "1_1") (pintype "passive"))
      (node (ref "C42") (pin "1") (pinfunction "1_1") (pintype "passive"))
      (node (ref "D2") (pin "C") (pinfunction "C_C") (pintype "passive"))
      (node (ref "FT232RL") (pin "20") (pinfunction "VCC_20") (pintype "power_in"))
      (node (ref "L2") (pin "2") (pinfunction "2_2") (pintype "passive"))
      (node (ref "PAM8406") (pin "13") (pinfunction "PVDDR_13") (pintype "bidirectional"))
      (node (ref "PAM8406") (pin "4") (pinfunction "PVDDL_4") (pintype "bidirectional"))
      (node (ref "PAM8406") (pin "6") (pinfunction "VDD_6") (pintype "bidirectional"))
      (node (ref "PAM8406") (pin "9") (pinfunction "MODE_9") (pintype "input"))
      (node (ref "PICKIT") (pin "2") (pinfunction "2_2") (pintype "bidirectional"))
      (node (ref "R10") (pin "2") (pinfunction "2_2") (pintype "passive"))
      (node (ref "XC6210") (pin "1") (pinfunction "VIN_1") (pintype "power_in"))
      (node (ref "XC6210") (pin "3") (pinfunction "CE_3") (pintype "power_in"))
    )
    (net (code "4") (name "12V") (class "Default")
      (node (ref "C5") (pin "1") (pinfunction "1_1") (pintype "passive"))
      (node (ref "Q2") (pin "2") (pinfunction "S_2") (pintype "bidirectional"))
      (node (ref "R2") (pin "2") (pinfunction "2_2") (pintype "passive"))
      (node (ref "R35") (pin "1") (pinfunction "1_1") (pintype "passive"))
      (node (ref "XC6702") (pin "1") (pinfunction "VOUT_1") (pintype "power_in"))
    )
    (net (code "5") (name "AGND") (class "Default")
      (node (ref "C45") (pin "2") (pinfunction "2_2") (pintype "passive"))
      (node (ref "C46") (pin "2") (pinfunction "2_2") (pintype "passive"))
      (node (ref "C47") (pin "2") (pinfunction "2_2") (pintype "passive"))
      (node (ref "C48") (pin "2") (pinfunction "2_2") (pintype "passive"))
      (node (ref "C49") (pin "1") (pinfunction "1_1") (pintype "passive"))
      (node (ref "C51") (pin "2") (pinfunction "2_2") (pintype "passive"))
      (node (ref "C52") (pin "2") (pinfunction "2_2") (pintype "passive"))
      (node (ref "PCM5122") (pin "10") (pinfunction "VCOM/DEMP_10") (pintype "input"))
      (node (ref "PCM5122") (pin "3") (pinfunction "CPGND_3") (pintype "bidirectional"))
      (node (ref "PCM5122") (pin "9") (pinfunction "AGND_9") (pintype "bidirectional"))
      (node (ref "SH1") (pin "2") (pinfunction "P$2_2") (pintype "bidirectional"))
      (node (ref "SPKR_OUT") (pin "2") (pinfunction "2_2") (pintype "bidirectional"))
      (node (ref "SPKR_OUT") (pin "5") (pinfunction "5_5") (pintype "bidirectional"))
    )
    (net (code "6") (name "BT_DATA_IO") (class "Default")
      (node (ref "BC127") (pin "25") (pinfunction "PIO_5/PCM2_OUT_25") (pintype "bidirectional"))
      (node (ref "PIC24FJ1024GA606") (pin "64") (pinfunction "HLVDIN/CTED8/PMD4/RE4_64") (pintype "bidirectional"))
    )
    (net (code "7") (name "BT_DOUT") (class "Default")
      (node (ref "BC127") (pin "48") (pinfunction "PCM1_OUT_48") (pintype "bidirectional"))
      (node (ref "C34") (pin "2") (pinfunction "2_2") (pintype "passive"))
      (node (ref "R34") (pin "2") (pinfunction "2_2") (pintype "passive"))
    )
    (net (code "8") (name "BT_MIC_L") (class "Default")
      (node (ref "BC127") (pin "20") (pinfunction "MIC_LN_20") (pintype "input"))
      (node (ref "C35") (pin "1") (pinfunction "1_1") (pintype "passive"))
      (node (ref "MIC_IN") (pin "TIP") (pinfunction "LEFT_TIP") (pintype "bidirectional"))
      (node (ref "R23") (pin "1") (pinfunction "1_1") (pintype "passive"))
    )
    (net (code "9") (name "BT_URX") (class "Default")
      (node (ref "PIC24FJ1024GA606") (pin "5") (pinfunction "C1INC/RP26/OCM1B/PMA4/RG7_5") (pintype "bidirectional"))
      (node (ref "R25") (pin "1") (pinfunction "1_1") (pintype "passive"))
      (node (ref "TMUX154E") (pin "2") (pinfunction "A0_2") (pintype "bidirectional"))
    )
    (net (code "10") (name "BT_UTX") (class "Default")
      (node (ref "BC127") (pin "41") (pinfunction "UART_TX_41") (pintype "output"))
      (node (ref "PIC24FJ1024GA606") (pin "4") (pinfunction "C1IND/RP21/ICM1/OCM1A/PMA5/RG6_4") (pintype "bidirectional"))
      (node (ref "R26") (pin "1") (pinfunction "1_1") (pintype "passive"))
      (node (ref "TMUX154E") (pin "8") (pinfunction "B0_8") (pintype "bidirectional"))
    )
    (net (code "11") (name "CHG_EXT") (class "Default")
      (node (ref "BC127") (pin "29") (pinfunction "CHG_EXT_29") (pintype "power_in"))
    )
    (net (code "12") (name "DAC_OUT_L") (class "Default")
      (node (ref "FB3") (pin "1") (pinfunction "1_1") (pintype "bidirectional"))
      (node (ref "PCM5122") (pin "6") (pinfunction "OUTL_6") (pintype "output"))
      (node (ref "R38") (pin "1") (pinfunction "1_1") (pintype "passive"))
    )
    (net (code "13") (name "EE_CS") (class "Default")
      (node (ref "25LC1024") (pin "1") (pinfunction "CE_1") (pintype "bidirectional"))
      (node (ref "PIC24FJ1024GA606") (pin "42") (pinfunction "CLC4OUT/RP2/U6RTS/U6BCLK/ICM5/RD8_42") (pintype "bidirectional"))
      (node (ref "R11") (pin "1") (pinfunction "1_1") (pintype "passive"))
    )
    (net (code "14") (name "EE_SCK") (class "Default")
      (node (ref "25LC1024") (pin "6") (pinfunction "SCK_6") (pintype "bidirectional"))
      (node (ref "PIC24FJ1024GA606") (pin "33") (pinfunction "RP16/RF3_33") (pintype "bidirectional"))
    )
    (net (code "15") (name "EE_SI") (class "Default")
      (node (ref "25LC1024") (pin "5") (pinfunction "SI_5") (pintype "bidirectional"))
      (node (ref "PIC24FJ1024GA606") (pin "34") (pinfunction "RP30/RF2_34") (pintype "bidirectional"))
    )
    (net (code "16") (name "EE_SO") (class "Default")
      (node (ref "25LC1024") (pin "2") (pinfunction "SO_2") (pintype "bidirectional"))
      (node (ref "PIC24FJ1024GA606") (pin "43") (pinfunction "RP4/PMACK2/RD9_43") (pintype "bidirectional"))
    )
    (net (code "17") (name "GND") (class "Default")
      (node (ref "25LC1024") (pin "4") (pinfunction "VSS_4") (pintype "power_in"))
      (node (ref "BC127") (pin "1") (pinfunction "GND_1") (pintype "bidirectional"))
      (node (ref "BC127") (pin "11") (pinfunction "GND_11") (pintype "bidirectional"))
      (node (ref "BC127") (pin "2") (pinfunction "GND_2") (pintype "bidirectional"))
      (node (ref "BC127") (pin "22") (pinfunction "GND_22") (pintype "bidirectional"))
      (node (ref "BC127") (pin "27") (pinfunction "GND_27") (pintype "bidirectional"))
      (node (ref "BC127") (pin "3") (pinfunction "GND_3") (pintype "bidirectional"))
      (node (ref "BC127") (pin "4") (pinfunction "GND_4") (pintype "bidirectional"))
      (node (ref "BC127") (pin "45") (pinfunction "SPI_PCM#_45") (pintype "input"))
      (node (ref "C1") (pin "2") (pinfunction "2_2") (pintype "passive"))
      (node (ref "C10") (pin "2") (pinfunction "2_2") (pintype "passive"))
      (node (ref "C11") (pin "2") (pinfunction "2_2") (pintype "passive"))
      (node (ref "C12") (pin "2") (pinfunction "2_2") (pintype "passive"))
      (node (ref "C13") (pin "2") (pinfunction "2_2") (pintype "passive"))
      (node (ref "C14") (pin "2") (pinfunction "2_2") (pintype "passive"))
      (node (ref "C15") (pin "1") (pinfunction "1_1") (pintype "passive"))
      (node (ref "C16") (pin "1") (pinfunction "1_1") (pintype "passive"))
      (node (ref "C17") (pin "1") (pinfunction "1_1") (pintype "passive"))
      (node (ref "C18") (pin "2") (pinfunction "2_2") (pintype "passive"))
      (node (ref "C19") (pin "2") (pinfunction "2_2") (pintype "passive"))
      (node (ref "C2") (pin "2") (pinfunction "2_2") (pintype "passive"))
      (node (ref "C20") (pin "1") (pinfunction "1_1") (pintype "passive"))
      (node (ref "C21") (pin "1") (pinfunction "1_1") (pintype "passive"))
      (node (ref "C22") (pin "2") (pinfunction "2_2") (pintype "passive"))
      (node (ref "C23") (pin "2") (pinfunction "2_2") (pintype "passive"))
      (node (ref "C24") (pin "2") (pinfunction "2_2") (pintype "passive"))
      (node (ref "C25") (pin "2") (pinfunction "2_2") (pintype "passive"))
      (node (ref "C26") (pin "2") (pinfunction "2_2") (pintype "passive"))
      (node (ref "C27") (pin "2") (pinfunction "2_2") (pintype "passive"))
      (node (ref "C28") (pin "2") (pinfunction "2_2") (pintype "passive"))
      (node (ref "C3") (pin "2") (pinfunction "2_2") (pintype "passive"))
      (node (ref "C30") (pin "2") (pinfunction "2_2") (pintype "passive"))
      (node (ref "C31") (pin "2") (pinfunction "2_2") (pintype "passive"))
      (node (ref "C32") (pin "2") (pinfunction "2_2") (pintype "passive"))
      (node (ref "C33") (pin "2") (pinfunction "2_2") (pintype "passive"))
      (node (ref "C36") (pin "2") (pinfunction "2_2") (pintype "passive"))
      (node (ref "C37") (pin "2") (pinfunction "2_2") (pintype "passive"))
      (node (ref "C38") (pin "2") (pinfunction "2_2") (pintype "passive"))
      (node (ref "C39") (pin "2") (pinfunction "2_2") (pintype "passive"))
      (node (ref "C4") (pin "2") (pinfunction "2_2") (pintype "passive"))
      (node (ref "C40") (pin "2") (pinfunction "2_2") (pintype "passive"))
      (node (ref "C41") (pin "2") (pinfunction "2_2") (pintype "passive"))
      (node (ref "C42") (pin "2") (pinfunction "2_2") (pintype "passive"))
      (node (ref "C44") (pin "2") (pinfunction "2_2") (pintype "passive"))
      (node (ref "C5") (pin "2") (pinfunction "2_2") (pintype "passive"))
      (node (ref "C53") (pin "2") (pinfunction "2_2") (pintype "passive"))
      (node (ref "C54") (pin "2") (pinfunction "2_2") (pintype "passive"))
      (node (ref "C55") (pin "2") (pinfunction "2_2") (pintype "passive"))
      (node (ref "C56") (pin "2") (pinfunction "2_2") (pintype "passive"))
      (node (ref "C6") (pin "2") (pinfunction "2_2") (pintype "passive"))
      (node (ref "C7") (pin "2") (pinfunction "2_2") (pintype "passive"))
      (node (ref "C9") (pin "2") (pinfunction "2_2") (pintype "passive"))
      (node (ref "DSP_OUT") (pin "1") (pinfunction "GND_1") (pintype "bidirectional"))
      (node (ref "DSP_OUT") (pin "2") (pinfunction "GND_2") (pintype "bidirectional"))
      (node (ref "DSP_OUT") (pin "3") (pinfunction "GND_3") (pintype "bidirectional"))
      (node (ref "DSP_OUT") (pin "4") (pinfunction "GND_4") (pintype "bidirectional"))
      (node (ref "FT232RL") (pin "18") (pinfunction "GND18_18") (pintype "power_in"))
      (node (ref "FT232RL") (pin "21") (pinfunction "GND21_21") (pintype "power_in"))
      (node (ref "FT232RL") (pin "25") (pinfunction "AGND_25") (pintype "power_in"))
      (node (ref "FT232RL") (pin "26") (pinfunction "TEST_26") (pintype "input"))
      (node (ref "FT232RL") (pin "7") (pinfunction "GND7_7") (pintype "power_in"))
      (node (ref "H1") (pin "B2,0") (pinfunction "MOUNT_B2,0") (pintype "passive"))
      (node (ref "H2") (pin "B2,0") (pinfunction "MOUNT_B2,0") (pintype "passive"))
      (node (ref "H3") (pin "B2,0") (pinfunction "MOUNT_B2,0") (pintype "passive"))
      (node (ref "H4") (pin "B2,0") (pinfunction "MOUNT_B2,0") (pintype "passive"))
      (node (ref "L1") (pin "2") (pinfunction "2_2") (pintype "passive"))
      (node (ref "L1") (pin "3") (pinfunction "3_3") (pintype "passive"))
      (node (ref "MIC_IN") (pin "SLEEVE") (pinfunction "SLEEVE_SLEEVE") (pintype "bidirectional"))
      (node (ref "MPQ4420") (pin "4") (pinfunction "GND_4") (pintype "bidirectional"))
      (node (ref "PAM8406") (pin "10") (pinfunction "INR_10") (pintype "input"))
      (node (ref "PAM8406") (pin "11") (pinfunction "GND_11") (pintype "bidirectional"))
      (node (ref "PAM8406") (pin "15") (pinfunction "PGNDR_15") (pintype "bidirectional"))
      (node (ref "PAM8406") (pin "2") (pinfunction "PGNDL_2") (pintype "bidirectional"))
      (node (ref "PCM5122") (pin "16") (pinfunction "ADR2/GPIO2/DOUT_16") (pintype "bidirectional"))
      (node (ref "PCM5122") (pin "17") (pinfunction "MODE1_17") (pintype "bidirectional"))
      (node (ref "PCM5122") (pin "24") (pinfunction "ADR1/MISO/FMT_24") (pintype "input"))
      (node (ref "PCM5122") (pin "27") (pinfunction "DGND_27") (pintype "bidirectional"))
      (node (ref "PIC24FJ1024GA606") (pin "20") (pinfunction "AVSS_20") (pintype "power_in"))
      (node (ref "PIC24FJ1024GA606") (pin "25") (pinfunction "VSS_25") (pintype "power_in"))
      (node (ref "PIC24FJ1024GA606") (pin "41") (pinfunction "VSS_41") (pintype "power_in"))
      (node (ref "PIC24FJ1024GA606") (pin "9") (pinfunction "VSS_9") (pintype "power_in"))
      (node (ref "PICKIT") (pin "4") (pinfunction "4_4") (pintype "bidirectional"))
      (node (ref "PWR") (pin "-") (pinfunction "C_-") (pintype "passive"))
      (node (ref "PWR_IN") (pin "1") (pinfunction "1_1") (pintype "passive"))
      (node (ref "Q1") (pin "2") (pinfunction "S_2") (pintype "bidirectional"))
      (node (ref "Q3") (pin "2") (pinfunction "S_2") (pintype "bidirectional"))
      (node (ref "R27") (pin "1") (pinfunction "1_1") (pintype "passive"))
      (node (ref "R3") (pin "1") (pinfunction "1_1") (pintype "passive"))
      (node (ref "R31") (pin "1") (pinfunction "1_1") (pintype "passive"))
      (node (ref "R33") (pin "1") (pinfunction "1_1") (pintype "passive"))
      (node (ref "R34") (pin "1") (pinfunction "1_1") (pintype "passive"))
      (node (ref "R4") (pin "1") (pinfunction "1_1") (pintype "passive"))
      (node (ref "R9") (pin "1") (pinfunction "1_1") (pintype "passive"))
      (node (ref "RECOVERY") (pin "1") (pinfunction "1_1") (pintype "passive"))
      (node (ref "SH1") (pin "1") (pinfunction "P$1_1") (pintype "bidirectional"))
      (node (ref "TCU_IO") (pin "4") (pinfunction "4_4") (pintype "bidirectional"))
      (node (ref "TH3122") (pin "12") (pinfunction "GND3_12") (pintype "passive"))
      (node (ref "TH3122") (pin "13") (pinfunction "GND4_13") (pintype "passive"))
      (node (ref "TH3122") (pin "3") (pinfunction "VTR_3") (pintype "input"))
      (node (ref "TH3122") (pin "4") (pinfunction "GND1_4") (pintype "passive"))
      (node (ref "TH3122") (pin "5") (pinfunction "GND2_5") (pintype "passive"))
      (node (ref "TH3122") (pin "7") (pinfunction "SI_7") (pintype "bidirectional"))
      (node (ref "TMUX154E") (pin "5") (pinfunction "GND_5") (pintype "power_in"))
      (node (ref "TMUX154E") (pin "9") (pinfunction "EN_9") (pintype "input"))
      (node (ref "USB") (pin "5") (pinfunction "GND_5") (pintype "power_in"))
      (node (ref "USB") (pin "Z1") (pinfunction "SHIELD_Z1") (pintype "bidirectional"))
      (node (ref "USB") (pin "Z2") (pinfunction "SHIELD_Z2") (pintype "bidirectional"))
      (node (ref "USB") (pin "Z3") (pinfunction "SHIELD_Z3") (pintype "bidirectional"))
      (node (ref "USB") (pin "Z4") (pinfunction "SHIELD_Z4") (pintype "bidirectional"))
      (node (ref "WM8804") (pin "18") (pinfunction "DGND_18") (pintype "power_in"))
      (node (ref "WM8804") (pin "8") (pinfunction "PGND_8") (pintype "power_in"))
      (node (ref "XC6210") (pin "2") (pinfunction "GND_2") (pintype "power_in"))
      (node (ref "XC6702") (pin "2") (pinfunction "GND_2") (pintype "power_in"))
    )
    (net (code "18") (name "I2S_CLK") (class "Default")
      (node (ref "PCM5122") (pin "21") (pinfunction "BCK_21") (pintype "input"))
      (node (ref "WM8804") (pin "14") (pinfunction "BCLK_14") (pintype "bidirectional"))
    )
    (net (code "19") (name "I2S_DOUT") (class "Default")
      (node (ref "PCM5122") (pin "22") (pinfunction "DIN_22") (pintype "input"))
      (node (ref "WM8804") (pin "12") (pinfunction "DOUT_12") (pintype "output"))
    )
    (net (code "20") (name "I2S_LRCK") (class "Default")
      (node (ref "PCM5122") (pin "23") (pinfunction "LRCK_23") (pintype "input"))
      (node (ref "WM8804") (pin "15") (pinfunction "LRCLK_15") (pintype "bidirectional"))
    )
    (net (code "21") (name "I2S_SCK") (class "Default")
      (node (ref "PCM5122") (pin "20") (pinfunction "SCK_20") (pintype "input"))
      (node (ref "WM8804") (pin "16") (pinfunction "MCLK_16") (pintype "bidirectional"))
    )
    (net (code "22") (name "IBUS") (class "Default")
      (node (ref "PWR_IN") (pin "3") (pinfunction "3_3") (pintype "passive"))
      (node (ref "R14") (pin "1") (pinfunction "1_1") (pintype "passive"))
    )
    (net (code "23") (name "IBUS_5V") (class "Default")
      (node (ref "C21") (pin "2") (pinfunction "2_2") (pintype "passive"))
      (node (ref "R6") (pin "2") (pinfunction "2_2") (pintype "passive"))
      (node (ref "TH3122") (pin "16") (pinfunction "VCC_16") (pintype "passive"))
    )
    (net (code "24") (name "IBUS_EN") (class "Default")
      (node (ref "PIC24FJ1024GA606") (pin "59") (pinfunction "RF1_59") (pintype "bidirectional"))
      (node (ref "TH3122") (pin "2") (pinfunction "EN_2") (pintype "input"))
    )
    (net (code "25") (name "IBUS_URX") (class "Default")
      (node (ref "PIC24FJ1024GA606") (pin "45") (pinfunction "RP12/PMA14/PMCS1/RD11_45") (pintype "bidirectional"))
      (node (ref "TH3122") (pin "10") (pinfunction "RXD_10") (pintype "output"))
    )
    (net (code "26") (name "IBUS_USTA") (class "Default")
      (node (ref "PIC24FJ1024GA606") (pin "46") (pinfunction "CLC3OUT/RP11/U6CTS/ICM6/RD0_46") (pintype "bidirectional"))
      (node (ref "TH3122") (pin "9") (pinfunction "SEN/STA_9") (pintype "bidirectional"))
    )
    (net (code "27") (name "IBUS_UTX") (class "Default")
      (node (ref "PIC24FJ1024GA606") (pin "44") (pinfunction "RP3/PMA15/PMCS2/RD10_44") (pintype "bidirectional"))
      (node (ref "TH3122") (pin "11") (pinfunction "TXD_11") (pintype "input"))
    )
    (net (code "28") (name "MCU_MCLR") (class "Default")
      (node (ref "PIC24FJ1024GA606") (pin "7") (pinfunction "MCLR_7") (pintype "bidirectional"))
      (node (ref "PICKIT") (pin "6") (pinfunction "6_6") (pintype "bidirectional"))
      (node (ref "R12") (pin "2") (pinfunction "2_2") (pintype "passive"))
    )
    (net (code "29") (name "MCU_PGC") (class "Default")
      (node (ref "PIC24FJ1024GA606") (pin "15") (pinfunction "PGEC1_15") (pintype "bidirectional"))
      (node (ref "PICKIT") (pin "5") (pinfunction "5_5") (pintype "bidirectional"))
    )
    (net (code "30") (name "MCU_PGD") (class "Default")
      (node (ref "PIC24FJ1024GA606") (pin "16") (pinfunction "PGED1_16") (pintype "bidirectional"))
      (node (ref "PICKIT") (pin "3") (pinfunction "3_3") (pintype "bidirectional"))
    )
    (net (code "31") (name "MCU_RECOV") (class "Default")
      (node (ref "PIC24FJ1024GA606") (pin "53") (pinfunction "RP20/PMRD/PMWR/RD5_53") (pintype "bidirectional"))
      (node (ref "R15") (pin "1") (pinfunction "1_1") (pintype "passive"))
      (node (ref "RECOVERY") (pin "2") (pinfunction "2_2") (pintype "passive"))
    )
    (net (code "32") (name "MCU_SCK3") (class "Default")
      (node (ref "PCM5122") (pin "12") (pinfunction "SCL/MC/ATT1_12") (pintype "bidirectional"))
      (node (ref "PIC24FJ1024GA606") (pin "2") (pinfunction "SCL3/IC5/PMD6/RE6_2") (pintype "bidirectional"))
      (node (ref "R32") (pin "2") (pinfunction "2_2") (pintype "passive"))
      (node (ref "WM8804") (pin "1") (pinfunction "SCLK_1") (pintype "input"))
    )
    (net (code "33") (name "MCU_SDA3") (class "Default")
      (node (ref "PCM5122") (pin "11") (pinfunction "SDA/MOSI/ATT2_11") (pintype "bidirectional"))
      (node (ref "PIC24FJ1024GA606") (pin "3") (pinfunction "SDA3/IC6/PMD7/RE7_3") (pintype "bidirectional"))
      (node (ref "R30") (pin "2") (pinfunction "2_2") (pintype "passive"))
      (node (ref "WM8804") (pin "3") (pinfunction "SDIN/HWMODE_3") (pintype "input"))
    )
    (net (code "34") (name "MCU_TEL_MUTE") (class "Default")
      (node (ref "PIC24FJ1024GA606") (pin "62") (pinfunction "PMD2/RE2_62") (pintype "bidirectional"))
      (node (ref "Q1") (pin "1") (pinfunction "G_1") (pintype "bidirectional"))
      (node (ref "R4") (pin "2") (pinfunction "2_2") (pintype "passive"))
    )
    (net (code "35") (name "MCU_TEL_ON") (class "Default")
      (node (ref "PIC24FJ1024GA606") (pin "18") (pinfunction "PGED2/AN7/RP7/U6TX/RB7_18") (pintype "bidirectional"))
      (node (ref "Q3") (pin "1") (pinfunction "G_1") (pintype "bidirectional"))
      (node (ref "R3") (pin "2") (pinfunction "2_2") (pintype "passive"))
    )
    (net (code "36") (name "MCU_URX") (class "Default")
      (node (ref "PIC24FJ1024GA606") (pin "50") (pinfunction "RP23/PMACK1/RD2_50") (pintype "bidirectional"))
      (node (ref "R16") (pin "1") (pinfunction "1_1") (pintype "passive"))
      (node (ref "TMUX154E") (pin "3") (pinfunction "A1_3") (pintype "bidirectional"))
    )
    (net (code "37") (name "MCU_UTX") (class "Default")
      (node (ref "PIC24FJ1024GA606") (pin "49") (pinfunction "RP24/U5TX/ICM4/RD1_49") (pintype "bidirectional"))
      (node (ref "R18") (pin "1") (pinfunction "1_1") (pintype "passive"))
      (node (ref "TMUX154E") (pin "7") (pinfunction "B1_7") (pintype "bidirectional"))
    )
    (net (code "38") (name "Net-(BC127-MIC_BIAS)") (class "Default")
      (node (ref "BC127") (pin "17") (pinfunction "MIC_BIAS_17") (pintype "input"))
      (node (ref "BC127") (pin "21") (pinfunction "MIC_LP_21") (pintype "input"))
      (node (ref "R23") (pin "2") (pinfunction "2_2") (pintype "passive"))
    )
    (net (code "39") (name "Net-(BC127-RST#)") (class "Default")
      (node (ref "BC127") (pin "44") (pinfunction "RST#_44") (pintype "input"))
      (node (ref "R24") (pin "1") (pinfunction "1_1") (pintype "passive"))
    )
    (net (code "40") (name "Net-(BC127-UART_RX)") (class "Default")
      (node (ref "BC127") (pin "42") (pinfunction "UART_RX_42") (pintype "input"))
      (node (ref "R25") (pin "2") (pinfunction "2_2") (pintype "passive"))
    )
    (net (code "41") (name "Net-(BC127-VCHG)") (class "Default")
      (node (ref "BC127") (pin "30") (pinfunction "VCHG_30") (pintype "power_in"))
      (node (ref "C28") (pin "1") (pinfunction "1_1") (pintype "passive"))
      (node (ref "R22") (pin "1") (pinfunction "1_1") (pintype "passive"))
    )
    (net (code "42") (name "Net-(C8-Pad1)") (class "Default")
      (node (ref "C8") (pin "1") (pinfunction "1_1") (pintype "passive"))
      (node (ref "R7") (pin "2") (pinfunction "2_2") (pintype "passive"))
    )
    (net (code "43") (name "Net-(C18-Pad1)") (class "Default")
      (node (ref "C18") (pin "1") (pinfunction "1_1") (pintype "passive"))
      (node (ref "R12") (pin "1") (pinfunction "1_1") (pintype "passive"))
      (node (ref "R13") (pin "2") (pinfunction "2_2") (pintype "passive"))
    )
    (net (code "44") (name "Net-(C29-Pad2)") (class "Default")
      (node (ref "C29") (pin "2") (pinfunction "2_2") (pintype "passive"))
      (node (ref "R27") (pin "2") (pinfunction "2_2") (pintype "passive"))
      (node (ref "R28") (pin "1") (pinfunction "1_1") (pintype "passive"))
    )
    (net (code "45") (name "Net-(C43-Pad1)") (class "Default")
      (node (ref "C43") (pin "1") (pinfunction "1_1") (pintype "passive"))
      (node (ref "FB3") (pin "2") (pinfunction "2_2") (pintype "bidirectional"))
    )
    (net (code "46") (name "Net-(C43-Pad2)") (class "Default")
      (node (ref "C43") (pin "2") (pinfunction "2_2") (pintype "passive"))
      (node (ref "R36") (pin "1") (pinfunction "1_1") (pintype "passive"))
    )
    (net (code "47") (name "Net-(F1-IN)") (class "Default")
      (node (ref "F1") (pin "OUT") (pinfunction "IN_OUT") (pintype "bidirectional"))
      (node (ref "L1") (pin "1") (pinfunction "1_1") (pintype "passive"))
    )
    (net (code "48") (name "Net-(F1-OUT)") (class "Default")
      (node (ref "D1") (pin "C") (pinfunction "C_C") (pintype "passive"))
      (node (ref "F1") (pin "IN") (pinfunction "OUT_IN") (pintype "bidirectional"))
    )
    (net (code "49") (name "Net-(FT232RL-3V3OUT)") (class "Default")
      (node (ref "C27") (pin "1") (pinfunction "1_1") (pintype "passive"))
      (node (ref "FT232RL") (pin "17") (pinfunction "3V3OUT_17") (pintype "output"))
      (node (ref "FT232RL") (pin "4") (pinfunction "VCCIO_4") (pintype "power_in"))
    )
    (net (code "50") (name "Net-(FT232RL-RXLED)") (class "Default")
      (node (ref "FT232RL") (pin "22") (pinfunction "RXLED_22") (pintype "input"))
      (node (ref "TX") (pin "-") (pinfunction "C_-") (pintype "passive"))
    )
    (net (code "51") (name "Net-(FT232RL-TXLED)") (class "Default")
      (node (ref "FT232RL") (pin "23") (pinfunction "TXLED_23") (pintype "input"))
      (node (ref "RX") (pin "-") (pinfunction "C_-") (pintype "passive"))
    )
    (net (code "52") (name "Net-(MPQ4420-BS)") (class "Default")
      (node (ref "MPQ4420") (pin "5") (pinfunction "BS_5") (pintype "bidirectional"))
      (node (ref "R7") (pin "1") (pinfunction "1_1") (pintype "passive"))
    )
    (net (code "53") (name "Net-(MPQ4420-EN)") (class "Default")
      (node (ref "MPQ4420") (pin "6") (pinfunction "EN_6") (pintype "bidirectional"))
      (node (ref "R6") (pin "1") (pinfunction "1_1") (pintype "passive"))
    )
    (net (code "54") (name "Net-(MPQ4420-FB)") (class "Default")
      (node (ref "MPQ4420") (pin "8") (pinfunction "FB_8") (pintype "bidirectional"))
      (node (ref "R8") (pin "2") (pinfunction "2_2") (pintype "passive"))
    )
    (net (code "55") (name "Net-(MPQ4420-PG)") (class "Default")
      (node (ref "MPQ4420") (pin "1") (pinfunction "PG_1") (pintype "bidirectional"))
      (node (ref "R5") (pin "1") (pinfunction "1_1") (pintype "passive"))
    )
    (net (code "56") (name "Net-(MPQ4420-SW)") (class "Default")
      (node (ref "C8") (pin "2") (pinfunction "2_2") (pintype "passive"))
      (node (ref "L2") (pin "1") (pinfunction "1_1") (pintype "passive"))
      (node (ref "MPQ4420") (pin "3") (pinfunction "SW_3") (pintype "bidirectional"))
    )
    (net (code "57") (name "Net-(MPQ4420-VCC)") (class "Default")
      (node (ref "C7") (pin "1") (pinfunction "1_1") (pintype "passive"))
      (node (ref "MPQ4420") (pin "7") (pinfunction "VCC_7") (pintype "bidirectional"))
      (node (ref "R5") (pin "2") (pinfunction "2_2") (pintype "passive"))
    )
    (net (code "58") (name "Net-(PAM8406-INL)") (class "Default")
      (node (ref "PAM8406") (pin "7") (pinfunction "INL_7") (pintype "input"))
      (node (ref "R36") (pin "2") (pinfunction "2_2") (pintype "passive"))
    )
    (net (code "59") (name "Net-(PAM8406-OUT_L+)") (class "Default")
      (node (ref "FB1") (pin "1") (pinfunction "1_1") (pintype "bidirectional"))
      (node (ref "PAM8406") (pin "1") (pinfunction "OUT_L+_1") (pintype "output"))
    )
    (net (code "60") (name "Net-(PAM8406-OUT_L-)") (class "Default")
      (node (ref "FB2") (pin "1") (pinfunction "1_1") (pintype "bidirectional"))
      (node (ref "PAM8406") (pin "3") (pinfunction "OUT_L-_3") (pintype "output"))
    )
    (net (code "61") (name "Net-(PAM8406-VREF)") (class "Default")
      (node (ref "C44") (pin "1") (pinfunction "1_1") (pintype "passive"))
      (node (ref "PAM8406") (pin "8") (pinfunction "VREF_8") (pintype "output"))
    )
    (net (code "62") (name "Net-(PCM5122-CAPM)") (class "Default")
      (node (ref "C50") (pin "2") (pinfunction "2_2") (pintype "passive"))
      (node (ref "PCM5122") (pin "4") (pinfunction "CAPM_4") (pintype "output"))
    )
    (net (code "63") (name "Net-(PCM5122-CAPP)") (class "Default")
      (node (ref "C50") (pin "1") (pinfunction "1_1") (pintype "passive"))
      (node (ref "PCM5122") (pin "2") (pinfunction "CAPP_2") (pintype "output"))
    )
    (net (code "64") (name "Net-(PCM5122-LDOO)") (class "Default")
      (node (ref "C55") (pin "1") (pinfunction "1_1") (pintype "passive"))
      (node (ref "C56") (pin "1") (pinfunction "1_1") (pintype "passive"))
      (node (ref "PCM5122") (pin "26") (pinfunction "LDOO_26") (pintype "power_in"))
    )
    (net (code "65") (name "Net-(PCM5122-OUTR)") (class "Default")
      (node (ref "PCM5122") (pin "7") (pinfunction "OUTR_7") (pintype "output"))
      (node (ref "R37") (pin "1") (pinfunction "1_1") (pintype "passive"))
    )
    (net (code "66") (name "Net-(PCM5122-VNEG)") (class "Default")
      (node (ref "C49") (pin "2") (pinfunction "2_2") (pintype "passive"))
      (node (ref "PCM5122") (pin "5") (pinfunction "VNEG_5") (pintype "output"))
    )
    (net (code "67") (name "Net-(PIC24FJ1024GA606-PMD0{slash}RE0)") (class "Default")
      (node (ref "PIC24FJ1024GA606") (pin "60") (pinfunction "PMD0/RE0_60") (pintype "bidirectional"))
      (node (ref "R19") (pin "2") (pinfunction "2_2") (pintype "passive"))
    )
    (net (code "68") (name "Net-(PIC24FJ1024GA606-VCAP)") (class "Default")
      (node (ref "C19") (pin "1") (pinfunction "1_1") (pintype "passive"))
      (node (ref "PIC24FJ1024GA606") (pin "56") (pinfunction "VCAP_56") (pintype "passive"))
    )
    (net (code "69") (name "Net-(PWR-A)") (class "Default")
      (node (ref "PWR") (pin "+") (pinfunction "A_+") (pintype "passive"))
      (node (ref "R19") (pin "1") (pinfunction "1_1") (pintype "passive"))
    )
    (net (code "70") (name "Net-(Q2-D)") (class "Default")
      (node (ref "Q2") (pin "3") (pinfunction "D_3") (pintype "bidirectional"))
      (node (ref "R1") (pin "1") (pinfunction "1_1") (pintype "passive"))
    )
    (net (code "71") (name "Net-(Q2-G)") (class "Default")
      (node (ref "Q2") (pin "1") (pinfunction "G_1") (pintype "bidirectional"))
      (node (ref "Q3") (pin "3") (pinfunction "D_3") (pintype "bidirectional"))
      (node (ref "R2") (pin "1") (pinfunction "1_1") (pintype "passive"))
    )
    (net (code "72") (name "Net-(R10-Pad1)") (class "Default")
      (node (ref "R10") (pin "1") (pinfunction "1_1") (pintype "passive"))
      (node (ref "R8") (pin "1") (pinfunction "1_1") (pintype "passive"))
      (node (ref "R9") (pin "2") (pinfunction "2_2") (pintype "passive"))
    )
    (net (code "73") (name "Net-(RX-A)") (class "Default")
      (node (ref "R20") (pin "1") (pinfunction "1_1") (pintype "passive"))
      (node (ref "RX") (pin "+") (pinfunction "A_+") (pintype "passive"))
    )
    (net (code "74") (name "Net-(TH3122-IBUS)") (class "Default")
      (node (ref "C22") (pin "1") (pinfunction "1_1") (pintype "passive"))
      (node (ref "R14") (pin "2") (pinfunction "2_2") (pintype "passive"))
      (node (ref "TH3122") (pin "6") (pinfunction "IBUS_6") (pintype "bidirectional"))
    )
    (net (code "75") (name "Net-(TX-A)") (class "Default")
      (node (ref "R21") (pin "1") (pinfunction "1_1") (pintype "passive"))
      (node (ref "TX") (pin "+") (pinfunction "A_+") (pintype "passive"))
    )
    (net (code "76") (name "Net-(WM8804-CSB{slash}GPO1)") (class "Default")
      (node (ref "R33") (pin "2") (pinfunction "2_2") (pintype "passive"))
      (node (ref "WM8804") (pin "5") (pinfunction "CSB/GPO1_5") (pintype "input"))
    )
    (net (code "77") (name "Net-(WM8804-GPO0{slash}SWIFMODE)") (class "Default")
      (node (ref "R31") (pin "2") (pinfunction "2_2") (pintype "passive"))
      (node (ref "WM8804") (pin "2") (pinfunction "GPO0/SWIFMODE_2") (pintype "output"))
    )
    (net (code "78") (name "Net-(WM8804-RESETB)") (class "Default")
      (node (ref "R29") (pin "2") (pinfunction "2_2") (pintype "passive"))
      (node (ref "WM8804") (pin "6") (pinfunction "RESETB_6") (pintype "input"))
    )
    (net (code "79") (name "Net-(WM8804-RXO)") (class "Default")
      (node (ref "C34") (pin "1") (pinfunction "1_1") (pintype "passive"))
      (node (ref "WM8804") (pin "20") (pinfunction "RXO_20") (pintype "input"))
    )
    (net (code "80") (name "Net-(WM8804-TXO)") (class "Default")
      (node (ref "R28") (pin "2") (pinfunction "2_2") (pintype "passive"))
      (node (ref "WM8804") (pin "17") (pinfunction "TXO_17") (pintype "output"))
    )
    (net (code "81") (name "Net-(WM8804-XIN)") (class "Default")
      (node (ref "C31") (pin "1") (pinfunction "1_1") (pintype "passive"))
      (node (ref "WM8804") (pin "11") (pinfunction "XIN_11") (pintype "bidirectional"))
      (node (ref "X1") (pin "2") (pinfunction "2_2") (pintype "passive"))
    )
    (net (code "82") (name "Net-(WM8804-XOP)") (class "Default")
      (node (ref "C32") (pin "1") (pinfunction "1_1") (pintype "passive"))
      (node (ref "WM8804") (pin "10") (pinfunction "XOP_10") (pintype "bidirectional"))
      (node (ref "X1") (pin "1") (pinfunction "1_1") (pintype "passive"))
    )
    (net (code "83") (name "SPDIF_OUT") (class "Default")
      (node (ref "C29") (pin "1") (pinfunction "1_1") (pintype "passive"))
      (node (ref "DSP_OUT") (pin "P$1") (pinfunction "1_P$1") (pintype "passive"))
    )
    (net (code "84") (name "SPKR_OUT_L") (class "Default")
      (node (ref "C46") (pin "1") (pinfunction "1_1") (pintype "passive"))
      (node (ref "R38") (pin "2") (pinfunction "2_2") (pintype "passive"))
      (node (ref "SPKR_OUT") (pin "1") (pinfunction "1_1") (pintype "bidirectional"))
    )
    (net (code "85") (name "SPKR_OUT_R") (class "Default")
      (node (ref "C45") (pin "1") (pinfunction "1_1") (pintype "passive"))
      (node (ref "R37") (pin "2") (pinfunction "2_2") (pintype "passive"))
      (node (ref "SPKR_OUT") (pin "4") (pinfunction "4_4") (pintype "bidirectional"))
    )
    (net (code "86") (name "SYS_DTR") (class "Default")
      (node (ref "FT232RL") (pin "2") (pinfunction "DTR_2") (pintype "output"))
      (node (ref "PIC24FJ1024GA606") (pin "52") (pinfunction "RP25/PMWR/PMENB/RD4_52") (pintype "bidirectional"))
    )
    (net (code "87") (name "SYS_UART_SEL") (class "Default")
      (node (ref "PIC24FJ1024GA606") (pin "51") (pinfunction "RP22/ICM7/PMBE0/RD3_51") (pintype "bidirectional"))
      (node (ref "R17") (pin "2") (pinfunction "2_2") (pintype "passive"))
      (node (ref "TMUX154E") (pin "1") (pinfunction "SEL_1") (pintype "bidirectional"))
    )
    (net (code "88") (name "SYS_URX") (class "Default")
      (node (ref "FT232RL") (pin "5") (pinfunction "RXD_5") (pintype "input"))
      (node (ref "TMUX154E") (pin "6") (pinfunction "B_6") (pintype "bidirectional"))
    )
    (net (code "89") (name "SYS_USB_DN") (class "Default")
      (node (ref "FT232RL") (pin "16") (pinfunction "USBDM_16") (pintype "bidirectional"))
      (node (ref "USB") (pin "2") (pinfunction "D-_2") (pintype "bidirectional"))
    )
    (net (code "90") (name "SYS_USB_DP") (class "Default")
      (node (ref "FT232RL") (pin "15") (pinfunction "USBDP_15") (pintype "bidirectional"))
      (node (ref "USB") (pin "3") (pinfunction "D+_3") (pintype "bidirectional"))
    )
    (net (code "91") (name "SYS_UTX") (class "Default")
      (node (ref "FT232RL") (pin "1") (pinfunction "TXD_1") (pintype "output"))
      (node (ref "TMUX154E") (pin "4") (pinfunction "A_4") (pintype "bidirectional"))
    )
    (net (code "92") (name "TEL_AMP_SHDN") (class "Default")
      (node (ref "PAM8406") (pin "12") (pinfunction "SHDN_12") (pintype "input"))
      (node (ref "PIC24FJ1024GA606") (pin "63") (pinfunction "CTED9/PMD3/RE3_63") (pintype "bidirectional"))
    )
    (net (code "93") (name "TEL_MIC_L_OUT") (class "Default")
      (node (ref "C35") (pin "2") (pinfunction "2_2") (pintype "passive"))
      (node (ref "R35") (pin "2") (pinfunction "2_2") (pintype "passive"))
      (node (ref "TCU_IO") (pin "3") (pinfunction "3_3") (pintype "bidirectional"))
    )
    (net (code "94") (name "TEL_MUTE_IO") (class "Default")
      (node (ref "Q1") (pin "3") (pinfunction "D_3") (pintype "bidirectional"))
      (node (ref "TCU_IO") (pin "6") (pinfunction "6_6") (pintype "bidirectional"))
    )
    (net (code "95") (name "TEL_ON_IO") (class "Default")
      (node (ref "R1") (pin "2") (pinfunction "2_2") (pintype "passive"))
      (node (ref "TCU_IO") (pin "5") (pinfunction "5_5") (pintype "bidirectional"))
    )
    (net (code "96") (name "TEL_OUT_L+") (class "Default")
      (node (ref "C39") (pin "1") (pinfunction "1_1") (pintype "passive"))
      (node (ref "FB1") (pin "2") (pinfunction "2_2") (pintype "bidirectional"))
      (node (ref "TCU_IO") (pin "1") (pinfunction "1_1") (pintype "bidirectional"))
    )
    (net (code "97") (name "TEL_OUT_L-") (class "Default")
      (node (ref "C40") (pin "1") (pinfunction "1_1") (pintype "passive"))
      (node (ref "FB2") (pin "2") (pinfunction "2_2") (pintype "bidirectional"))
      (node (ref "TCU_IO") (pin "2") (pinfunction "2_2") (pintype "bidirectional"))
    )
    (net (code "98") (name "USB_5V") (class "Default")
      (node (ref "D2") (pin "A") (pinfunction "A_A") (pintype "passive"))
      (node (ref "USB") (pin "1") (pinfunction "VBUS_1") (pintype "power_in"))
    )
    (net (code "99") (name "VBAT") (class "Default")
      (node (ref "D1") (pin "A") (pinfunction "A_A") (pintype "passive"))
      (node (ref "PWR_IN") (pin "2") (pinfunction "2_2") (pintype "passive"))
    )
    (net (code "100") (name "VIN") (class "Default")
      (node (ref "C1") (pin "1") (pinfunction "1_1") (pintype "passive"))
      (node (ref "C10") (pin "1") (pinfunction "1_1") (pintype "passive"))
      (node (ref "C11") (pin "1") (pinfunction "1_1") (pintype "passive"))
      (node (ref "C23") (pin "1") (pinfunction "1_1") (pintype "passive"))
      (node (ref "C6") (pin "1") (pinfunction "1_1") (pintype "passive"))
      (node (ref "C9") (pin "1") (pinfunction "1_1") (pintype "passive"))
      (node (ref "L1") (pin "4") (pinfunction "4_4") (pintype "passive"))
      (node (ref "MPQ4420") (pin "2") (pinfunction "IN_2") (pintype "bidirectional"))
      (node (ref "TH3122") (pin "1") (pinfunction "VS_1") (pintype "power_in"))
      (node (ref "XC6702") (pin "3") (pinfunction "CE_3") (pintype "power_in"))
      (node (ref "XC6702") (pin "5") (pinfunction "VIN_5") (pintype "power_in"))
    )
    (net (code "101") (name "unconnected-(BC127-AIO-Pad12)") (class "Default")
      (node (ref "BC127") (pin "12") (pinfunction "AIO_12") (pintype "bidirectional"))
    )
    (net (code "102") (name "unconnected-(BC127-CAP_SENSE_1-Pad7)") (class "Default")
      (node (ref "BC127") (pin "7") (pinfunction "CAP_SENSE_1_7") (pintype "input"))
    )
    (net (code "103") (name "unconnected-(BC127-CAP_SENSE_2-Pad8)") (class "Default")
      (node (ref "BC127") (pin "8") (pinfunction "CAP_SENSE_2_8") (pintype "input"))
    )
    (net (code "104") (name "unconnected-(BC127-CAP_SENSE_3-Pad9)") (class "Default")
      (node (ref "BC127") (pin "9") (pinfunction "CAP_SENSE_3_9") (pintype "input"))
    )
    (net (code "105") (name "unconnected-(BC127-CAP_SENSE_4-Pad10)") (class "Default")
      (node (ref "BC127") (pin "10") (pinfunction "CAP_SENSE_4_10") (pintype "input"))
    )
    (net (code "106") (name "unconnected-(BC127-LED_0-Pad37)") (class "Default")
      (node (ref "BC127") (pin "37") (pinfunction "LED_0_37") (pintype "output"))
    )
    (net (code "107") (name "unconnected-(BC127-LED_1-Pad38)") (class "Default")
      (node (ref "BC127") (pin "38") (pinfunction "LED_1_38") (pintype "output"))
    )
    (net (code "108") (name "unconnected-(BC127-LED_2-Pad39)") (class "Default")
      (node (ref "BC127") (pin "39") (pinfunction "LED_2_39") (pintype "output"))
    )
    (net (code "109") (name "unconnected-(BC127-MIC_RN-Pad18)") (class "Default")
      (node (ref "BC127") (pin "18") (pinfunction "MIC_RN_18") (pintype "input"))
    )
    (net (code "110") (name "unconnected-(BC127-MIC_RP-Pad19)") (class "Default")
      (node (ref "BC127") (pin "19") (pinfunction "MIC_RP_19") (pintype "input"))
    )
    (net (code "111") (name "unconnected-(BC127-PCM1_CLK-Pad47)") (class "Default")
      (node (ref "BC127") (pin "47") (pinfunction "PCM1_CLK_47") (pintype "bidirectional"))
    )
    (net (code "112") (name "unconnected-(BC127-PCM1_IN-Pad49)") (class "Default")
      (node (ref "BC127") (pin "49") (pinfunction "PCM1_IN_49") (pintype "bidirectional"))
    )
    (net (code "113") (name "unconnected-(BC127-PCM1_SYNC-Pad46)") (class "Default")
      (node (ref "BC127") (pin "46") (pinfunction "PCM1_SYNC_46") (pintype "bidirectional"))
    )
    (net (code "114") (name "unconnected-(BC127-PIO_0-Pad23)") (class "Default")
      (node (ref "BC127") (pin "23") (pinfunction "PIO_0_23") (pintype "bidirectional"))
    )
    (net (code "115") (name "unconnected-(BC127-PIO_1-Pad24)") (class "Default")
      (node (ref "BC127") (pin "24") (pinfunction "PIO_1_24") (pintype "bidirectional"))
    )
    (net (code "116") (name "unconnected-(BC127-PIO_2-Pad50)") (class "Default")
      (node (ref "BC127") (pin "50") (pinfunction "PIO_2_50") (pintype "bidirectional"))
    )
    (net (code "117") (name "unconnected-(BC127-PIO_3-Pad51)") (class "Default")
      (node (ref "BC127") (pin "51") (pinfunction "PIO_3_51") (pintype "bidirectional"))
    )
    (net (code "118") (name "unconnected-(BC127-PIO_4{slash}PCM2_IN-Pad26)") (class "Default")
      (node (ref "BC127") (pin "26") (pinfunction "PIO_4/PCM2_IN_26") (pintype "bidirectional"))
    )
    (net (code "119") (name "unconnected-(BC127-PIO_6{slash}PCM2_SYNC-Pad5)") (class "Default")
      (node (ref "BC127") (pin "5") (pinfunction "PIO_6/PCM2_SYNC_5") (pintype "bidirectional"))
    )
    (net (code "120") (name "unconnected-(BC127-PIO_7{slash}PCM2_CLK-Pad6)") (class "Default")
      (node (ref "BC127") (pin "6") (pinfunction "PIO_7/PCM2_CLK_6") (pintype "bidirectional"))
    )
    (net (code "121") (name "unconnected-(BC127-SPKR_LN-Pad13)") (class "Default")
      (node (ref "BC127") (pin "13") (pinfunction "SPKR_LN_13") (pintype "output"))
    )
    (net (code "122") (name "unconnected-(BC127-SPKR_LP-Pad14)") (class "Default")
      (node (ref "BC127") (pin "14") (pinfunction "SPKR_LP_14") (pintype "output"))
    )
    (net (code "123") (name "unconnected-(BC127-SPKR_RN-Pad15)") (class "Default")
      (node (ref "BC127") (pin "15") (pinfunction "SPKR_RN_15") (pintype "output"))
    )
    (net (code "124") (name "unconnected-(BC127-SPKR_RP-Pad16)") (class "Default")
      (node (ref "BC127") (pin "16") (pinfunction "SPKR_RP_16") (pintype "output"))
    )
    (net (code "125") (name "unconnected-(BC127-UART_CTS-Pad40)") (class "Default")
      (node (ref "BC127") (pin "40") (pinfunction "UART_CTS_40") (pintype "input"))
    )
    (net (code "126") (name "unconnected-(BC127-UART_RTS-Pad43)") (class "Default")
      (node (ref "BC127") (pin "43") (pinfunction "UART_RTS_43") (pintype "output"))
    )
    (net (code "127") (name "unconnected-(BC127-USB_N-Pad35)") (class "Default")
      (node (ref "BC127") (pin "35") (pinfunction "USB_N_35") (pintype "bidirectional"))
    )
    (net (code "128") (name "unconnected-(BC127-USB_P-Pad36)") (class "Default")
      (node (ref "BC127") (pin "36") (pinfunction "USB_P_36") (pintype "bidirectional"))
    )
    (net (code "129") (name "unconnected-(BC127-VREGEN-Pad28)") (class "Default")
      (node (ref "BC127") (pin "28") (pinfunction "VREGEN_28") (pintype "output"))
    )
    (net (code "130") (name "unconnected-(FT232RL-CTS-Pad11)") (class "Default")
      (node (ref "FT232RL") (pin "11") (pinfunction "CTS_11") (pintype "input"))
    )
    (net (code "131") (name "unconnected-(FT232RL-DCD-Pad10)") (class "Default")
      (node (ref "FT232RL") (pin "10") (pinfunction "DCD_10") (pintype "input"))
    )
    (net (code "132") (name "unconnected-(FT232RL-DSR-Pad9)") (class "Default")
      (node (ref "FT232RL") (pin "9") (pinfunction "DSR_9") (pintype "input"))
    )
    (net (code "133") (name "unconnected-(FT232RL-OSCI-Pad27)") (class "Default")
      (node (ref "FT232RL") (pin "27") (pinfunction "OSCI_27") (pintype "input"))
    )
    (net (code "134") (name "unconnected-(FT232RL-OSCO-Pad28)") (class "Default")
      (node (ref "FT232RL") (pin "28") (pinfunction "OSCO_28") (pintype "output"))
    )
    (net (code "135") (name "unconnected-(FT232RL-PWREN-Pad14)") (class "Default")
      (node (ref "FT232RL") (pin "14") (pinfunction "PWREN_14") (pintype "input"))
    )
    (net (code "136") (name "unconnected-(FT232RL-RESET-Pad19)") (class "Default")
      (node (ref "FT232RL") (pin "19") (pinfunction "RESET_19") (pintype "input"))
    )
    (net (code "137") (name "unconnected-(FT232RL-RI-Pad6)") (class "Default")
      (node (ref "FT232RL") (pin "6") (pinfunction "RI_6") (pintype "input"))
    )
    (net (code "138") (name "unconnected-(FT232RL-RTS-Pad3)") (class "Default")
      (node (ref "FT232RL") (pin "3") (pinfunction "RTS_3") (pintype "output"))
    )
    (net (code "139") (name "unconnected-(FT232RL-SLEEP-Pad12)") (class "Default")
      (node (ref "FT232RL") (pin "12") (pinfunction "SLEEP_12") (pintype "input"))
    )
    (net (code "140") (name "unconnected-(FT232RL-TXDEN-Pad13)") (class "Default")
      (node (ref "FT232RL") (pin "13") (pinfunction "TXDEN_13") (pintype "input"))
    )
    (net (code "141") (name "unconnected-(MIC_IN-RIGHT-PadRING)") (class "Default")
      (node (ref "MIC_IN") (pin "RING") (pinfunction "RIGHT_RING") (pintype "bidirectional"))
    )
    (net (code "142") (name "unconnected-(PAM8406-MUTE-Pad5)") (class "Default")
      (node (ref "PAM8406") (pin "5") (pinfunction "MUTE_5") (pintype "input"))
    )
    (net (code "143") (name "unconnected-(PAM8406-OUT_R+-Pad16)") (class "Default")
      (node (ref "PAM8406") (pin "16") (pinfunction "OUT_R+_16") (pintype "output"))
    )
    (net (code "144") (name "unconnected-(PAM8406-OUT_R--Pad14)") (class "Default")
      (node (ref "PAM8406") (pin "14") (pinfunction "OUT_R-_14") (pintype "output"))
    )
    (net (code "145") (name "unconnected-(PCM5122-GPIO3{slash}AGNS-Pad15)") (class "Default")
      (node (ref "PCM5122") (pin "15") (pinfunction "GPIO3/AGNS_15") (pintype "bidirectional"))
    )
    (net (code "146") (name "unconnected-(PCM5122-GPIO4{slash}MAST-Pad14)") (class "Default")
      (node (ref "PCM5122") (pin "14") (pinfunction "GPIO4/MAST_14") (pintype "bidirectional"))
    )
    (net (code "147") (name "unconnected-(PCM5122-GPIO5{slash}ATT0-Pad13)") (class "Default")
      (node (ref "PCM5122") (pin "13") (pinfunction "GPIO5/ATT0_13") (pintype "bidirectional"))
    )
    (net (code "148") (name "unconnected-(PCM5122-GPIO6{slash}FLT-Pad19)") (class "Default")
      (node (ref "PCM5122") (pin "19") (pinfunction "GPIO6/FLT_19") (pintype "input"))
    )
    (net (code "149") (name "unconnected-(PIC24FJ1024GA606-AN2{slash}CTCMP{slash}C2INB{slash}RP13{slash}CTED13{slash}RB2-Pad14)") (class "Default")
      (node (ref "PIC24FJ1024GA606") (pin "14") (pinfunction "AN2/CTCMP/C2INB/RP13/CTED13/RB2_14") (pintype "bidirectional"))
    )
    (net (code "150") (name "unconnected-(PIC24FJ1024GA606-AN3{slash}C2INA{slash}RB3-Pad13)") (class "Default")
      (node (ref "PIC24FJ1024GA606") (pin "13") (pinfunction "AN3/C2INA/RB3_13") (pintype "bidirectional"))
    )
    (net (code "151") (name "unconnected-(PIC24FJ1024GA606-AN8{slash}RP8{slash}PWRGT{slash}RB8-Pad21)") (class "Default")
      (node (ref "PIC24FJ1024GA606") (pin "21") (pinfunction "AN8/RP8/PWRGT/RB8_21") (pintype "bidirectional"))
    )
    (net (code "152") (name "unconnected-(PIC24FJ1024GA606-AN9{slash}TMPR{slash}RP9{slash}T1CK{slash}PMA7{slash}RB9-Pad22)") (class "Default")
      (node (ref "PIC24FJ1024GA606") (pin "22") (pinfunction "AN9/TMPR/RP9/T1CK/PMA7/RB9_22") (pintype "bidirectional"))
    )
    (net (code "153") (name "unconnected-(PIC24FJ1024GA606-AN14{slash}RP14{slash}CTED5{slash}CTPLS{slash}PMA1{slash}PMALH{slash}RB14-Pad29)") (class "Default")
      (node (ref "PIC24FJ1024GA606") (pin "29") (pinfunction "AN14/RP14/CTED5/CTPLS/PMA1/PMALH/RB14_29") (pintype "bidirectional"))
    )
    (net (code "154") (name "unconnected-(PIC24FJ1024GA606-AN15{slash}RP29{slash}CTED6{slash}PMA0{slash}PMALL{slash}RB15-Pad30)") (class "Default")
      (node (ref "PIC24FJ1024GA606") (pin "30") (pinfunction "AN15/RP29/CTED6/PMA0/PMALL/RB15_30") (pintype "bidirectional"))
    )
    (net (code "155") (name "unconnected-(PIC24FJ1024GA606-C1INC{slash}C2INC{slash}C3INC{slash}RP27{slash}OCM2B{slash}PMA2{slash}PMALU{slash}RG9-Pad8)") (class "Default")
      (node (ref "PIC24FJ1024GA606") (pin "8") (pinfunction "C1INC/C2INC/C3INC/RP27/OCM2B/PMA2/PMALU/RG9_8") (pintype "bidirectional"))
    )
    (net (code "156") (name "unconnected-(PIC24FJ1024GA606-C2IND{slash}RP19{slash}ICM2{slash}OCM2A{slash}PMA3{slash}RG8-Pad6)") (class "Default")
      (node (ref "PIC24FJ1024GA606") (pin "6") (pinfunction "C2IND/RP19/ICM2/OCM2A/PMA3/RG8_6") (pintype "bidirectional"))
    )
    (net (code "157") (name "unconnected-(PIC24FJ1024GA606-C3INA{slash}U5RTS{slash}U5BCLK{slash}OC5{slash}RD7-Pad55)") (class "Default")
      (node (ref "PIC24FJ1024GA606") (pin "55") (pinfunction "C3INA/U5RTS/U5BCLK/OC5/RD7_55") (pintype "bidirectional"))
    )
    (net (code "158") (name "unconnected-(PIC24FJ1024GA606-C3INB{slash}U5RX{slash}OC4{slash}RD6-Pad54)") (class "Default")
      (node (ref "PIC24FJ1024GA606") (pin "54") (pinfunction "C3INB/U5RX/OC4/RD6_54") (pintype "bidirectional"))
    )
    (net (code "159") (name "unconnected-(PIC24FJ1024GA606-IC4{slash}CTED4{slash}PMD5{slash}RE5-Pad1)") (class "Default")
      (node (ref "PIC24FJ1024GA606") (pin "1") (pinfunction "IC4/CTED4/PMD5/RE5_1") (pintype "bidirectional"))
    )
    (net (code "160") (name "unconnected-(PIC24FJ1024GA606-INT0{slash}RF6-Pad35)") (class "Default")
      (node (ref "PIC24FJ1024GA606") (pin "35") (pinfunction "INT0/RF6_35") (pintype "bidirectional"))
    )
    (net (code "161") (name "unconnected-(PIC24FJ1024GA606-N{slash}C-Pad57)") (class "Default")
      (node (ref "PIC24FJ1024GA606") (pin "57") (pinfunction "N/C_57") (pintype "no_connect"))
    )
    (net (code "162") (name "unconnected-(PIC24FJ1024GA606-OSCI{slash}CLKI{slash}RC12-Pad39)") (class "Default")
      (node (ref "PIC24FJ1024GA606") (pin "39") (pinfunction "OSCI/CLKI/RC12_39") (pintype "bidirectional"))
    )
    (net (code "163") (name "unconnected-(PIC24FJ1024GA606-OSCO{slash}CLKO{slash}RC15-Pad40)") (class "Default")
      (node (ref "PIC24FJ1024GA606") (pin "40") (pinfunction "OSCO/CLKO/RC15_40") (pintype "bidirectional"))
    )
    (net (code "164") (name "unconnected-(PIC24FJ1024GA606-PGEC2{slash}AN6{slash}RP6{slash}RB6-Pad17)") (class "Default")
      (node (ref "PIC24FJ1024GA606") (pin "17") (pinfunction "PGEC2/AN6/RP6/RB6_17") (pintype "bidirectional"))
    )
    (net (code "165") (name "unconnected-(PIC24FJ1024GA606-PGEC3{slash}AN5{slash}C1INA{slash}RP18{slash}ICM3{slash}OCM3A{slash}RB5-Pad11)") (class "Default")
      (node (ref "PIC24FJ1024GA606") (pin "11") (pinfunction "PGEC3/AN5/C1INA/RP18/ICM3/OCM3A/RB5_11") (pintype "bidirectional"))
    )
    (net (code "166") (name "unconnected-(PIC24FJ1024GA606-PGED3{slash}AN4{slash}C1INB{slash}RP28{slash}OCM3B{slash}RB4-Pad12)") (class "Default")
      (node (ref "PIC24FJ1024GA606") (pin "12") (pinfunction "PGED3/AN4/C1INB/RP28/OCM3B/RB4_12") (pintype "bidirectional"))
    )
    (net (code "167") (name "unconnected-(PIC24FJ1024GA606-PMD1{slash}RE1-Pad61)") (class "Default")
      (node (ref "PIC24FJ1024GA606") (pin "61") (pinfunction "PMD1/RE1_61") (pintype "bidirectional"))
    )
    (net (code "168") (name "unconnected-(PIC24FJ1024GA606-RP10{slash}SDA2{slash}PMA9{slash}RF4-Pad31)") (class "Default")
      (node (ref "PIC24FJ1024GA606") (pin "31") (pinfunction "RP10/SDA2/PMA9/RF4_31") (pintype "bidirectional"))
    )
    (net (code "169") (name "unconnected-(PIC24FJ1024GA606-RP17{slash}SCL2{slash}PMA8{slash}RF5-Pad32)") (class "Default")
      (node (ref "PIC24FJ1024GA606") (pin "32") (pinfunction "RP17/SCL2/PMA8/RF5_32") (pintype "bidirectional"))
    )
    (net (code "170") (name "unconnected-(PIC24FJ1024GA606-SCL1{slash}RG2-Pad37)") (class "Default")
      (node (ref "PIC24FJ1024GA606") (pin "37") (pinfunction "SCL1/RG2_37") (pintype "bidirectional"))
    )
    (net (code "171") (name "unconnected-(PIC24FJ1024GA606-SDA1{slash}RG3-Pad36)") (class "Default")
      (node (ref "PIC24FJ1024GA606") (pin "36") (pinfunction "SDA1/RG3_36") (pintype "bidirectional"))
    )
    (net (code "172") (name "unconnected-(PIC24FJ1024GA606-SOSCI{slash}C3IND{slash}RC13-Pad47)") (class "Default")
      (node (ref "PIC24FJ1024GA606") (pin "47") (pinfunction "SOSCI/C3IND/RC13_47") (pintype "bidirectional"))
    )
    (net (code "173") (name "unconnected-(PIC24FJ1024GA606-SOSCO{slash}C3INC{slash}RPI37{slash}PWRLCLK{slash}RC14-Pad48)") (class "Default")
      (node (ref "PIC24FJ1024GA606") (pin "48") (pinfunction "SOSCO/C3INC/RPI37/PWRLCLK/RC14_48") (pintype "bidirectional"))
    )
    (net (code "174") (name "unconnected-(PIC24FJ1024GA606-TCK{slash}AN12{slash}U6RX{slash}CTED2{slash}PMA11{slash}RB12-Pad27)") (class "Default")
      (node (ref "PIC24FJ1024GA606") (pin "27") (pinfunction "TCK/AN12/U6RX/CTED2/PMA11/RB12_27") (pintype "bidirectional"))
    )
    (net (code "175") (name "unconnected-(PIC24FJ1024GA606-TDI{slash}AN13{slash}CTED1{slash}PMA10{slash}RB13-Pad28)") (class "Default")
      (node (ref "PIC24FJ1024GA606") (pin "28") (pinfunction "TDI/AN13/CTED1/PMA10/RB13_28") (pintype "bidirectional"))
    )
    (net (code "176") (name "unconnected-(PIC24FJ1024GA606-TDO{slash}AN11{slash}REFI{slash}PMA12{slash}RB11-Pad24)") (class "Default")
      (node (ref "PIC24FJ1024GA606") (pin "24") (pinfunction "TDO/AN11/REFI/PMA12/RB11_24") (pintype "bidirectional"))
    )
    (net (code "177") (name "unconnected-(PIC24FJ1024GA606-TMS{slash}CVREF{slash}AN10{slash}PMA13{slash}RB10-Pad23)") (class "Default")
      (node (ref "PIC24FJ1024GA606") (pin "23") (pinfunction "TMS/CVREF/AN10/PMA13/RB10_23") (pintype "bidirectional"))
    )
    (net (code "178") (name "unconnected-(PIC24FJ1024GA606-U5CTS{slash}OC6{slash}RF0-Pad58)") (class "Default")
      (node (ref "PIC24FJ1024GA606") (pin "58") (pinfunction "U5CTS/OC6/RF0_58") (pintype "bidirectional"))
    )
    (net (code "179") (name "unconnected-(SPKR_OUT-Pad3)") (class "Default")
      (node (ref "SPKR_OUT") (pin "3") (pinfunction "3_3") (pintype "bidirectional"))
    )
    (net (code "180") (name "unconnected-(SPKR_OUT-Pad6)") (class "Default")
      (node (ref "SPKR_OUT") (pin "6") (pinfunction "6_6") (pintype "bidirectional"))
    )
    (net (code "181") (name "unconnected-(TH3122-RESET-Pad14)") (class "Default")
      (node (ref "TH3122") (pin "14") (pinfunction "RESET_14") (pintype "output"))
    )
    (net (code "182") (name "unconnected-(TH3122-SENSE-Pad15)") (class "Default")
      (node (ref "TH3122") (pin "15") (pinfunction "SENSE_15") (pintype "bidirectional"))
    )
    (net (code "183") (name "unconnected-(TH3122-SO-Pad8)") (class "Default")
      (node (ref "TH3122") (pin "8") (pinfunction "SO_8") (pintype "output"))
    )
    (net (code "184") (name "unconnected-(USB-ID-Pad4)") (class "Default")
      (node (ref "USB") (pin "4") (pinfunction "ID_4") (pintype "bidirectional"))
    )
    (net (code "185") (name "unconnected-(WM8804-CLKOUT-Pad9)") (class "Default")
      (node (ref "WM8804") (pin "9") (pinfunction "CLKOUT_9") (pintype "output"))
    )
    (net (code "186") (name "unconnected-(WM8804-DIN-Pad13)") (class "Default")
      (node (ref "WM8804") (pin "13") (pinfunction "DIN_13") (pintype "input"))
    )
    (net (code "187") (name "unconnected-(WM8804-SDOUT{slash}GPO2-Pad4)") (class "Default")
      (node (ref "WM8804") (pin "4") (pinfunction "SDOUT/GPO2_4") (pintype "output"))
    )
    (net (code "188") (name "unconnected-(XC6210-NC-Pad4)") (class "Default")
      (node (ref "XC6210") (pin "4") (pinfunction "NC_4") (pintype "no_connect"))
    )
    (net (code "189") (name "unconnected-(XC6702-NC-Pad4)") (class "Default")
      (node (ref "XC6702") (pin "4") (pinfunction "NC_4") (pintype "no_connect"))
    )
  )
)
